# ECU_Revisi.net
KiCad netlist of a schematic drawn in EasyEDA Pro
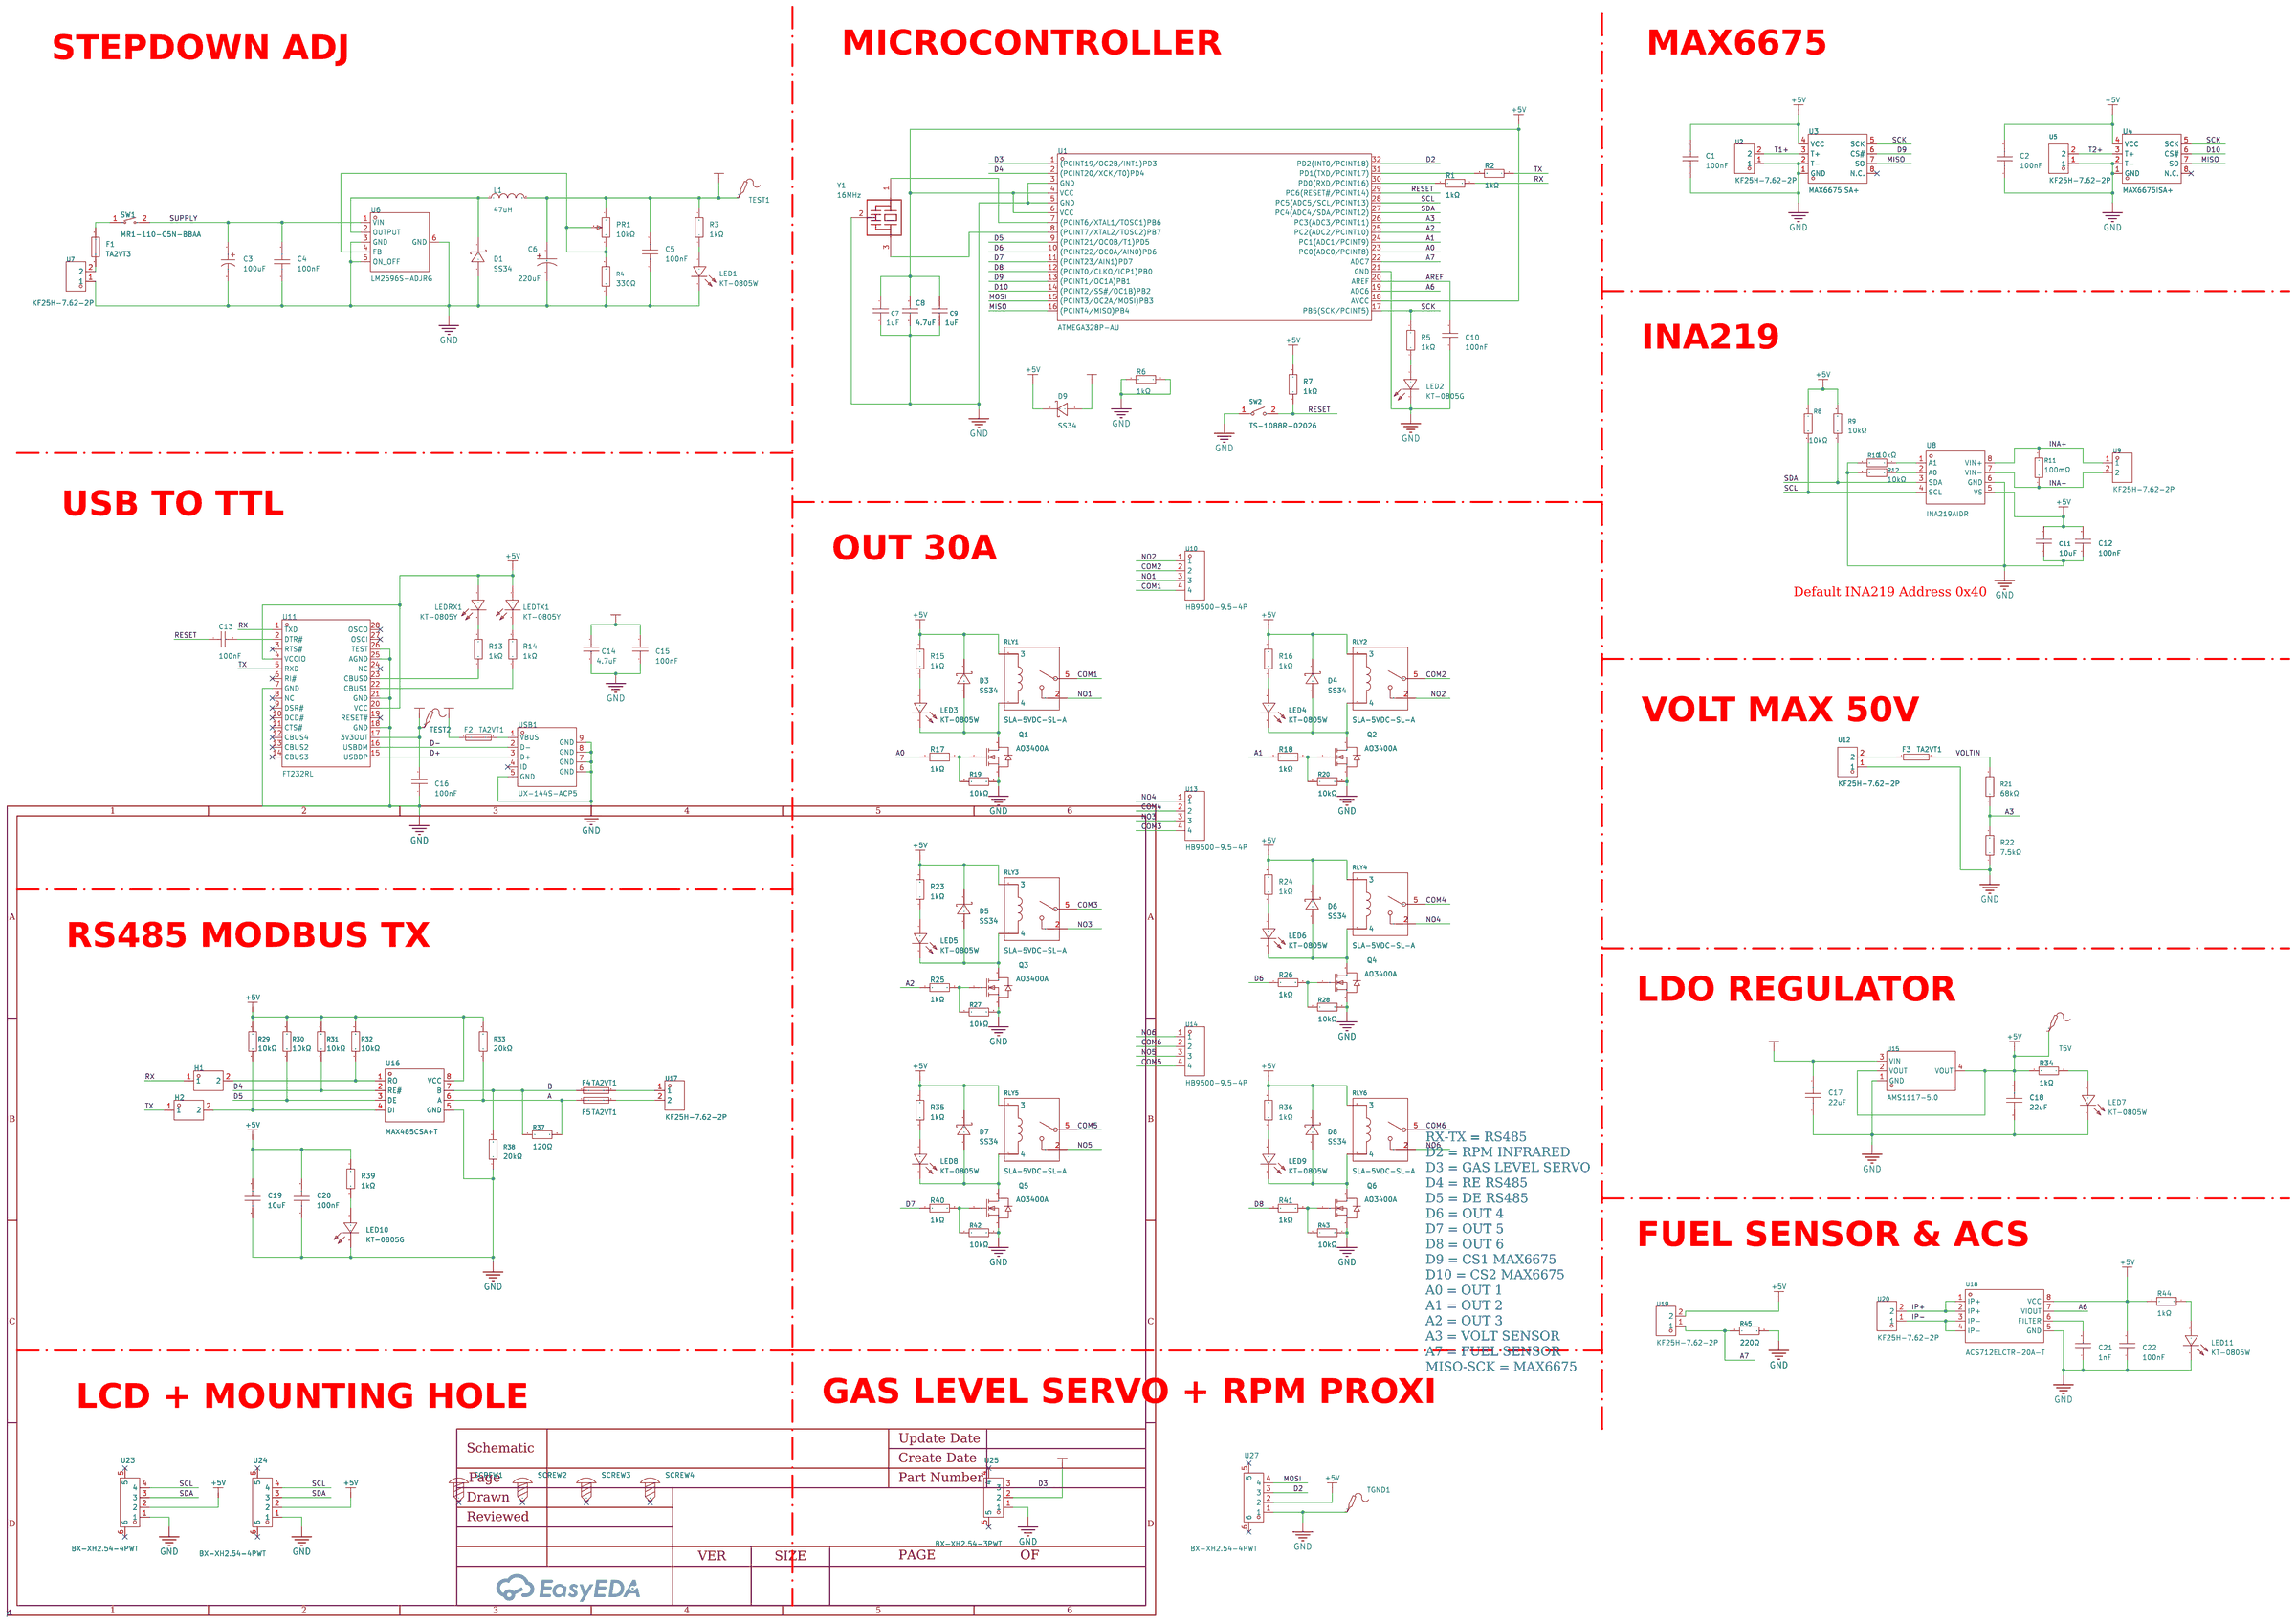
[diagram p0: schematic sheet]

(export (version "E")
  (design (tool "Eeschema 10.0.6"))
  (components
    (comp (ref "C1")
      (value "100nF")
      (footprint "easyedapro:C0805")
      (fields
        (field (name "Manufacturer Part") "CC0805KRX7R9BB104")
        (field (name "Manufacturer") "YAGEO(国巨)")
      )
      (libsource (lib "easyedapro") (part "CC0805KRX7R9BB104"))
    )
    (comp (ref "C2")
      (value "100nF")
      (footprint "easyedapro:C0805")
      (fields
        (field (name "Manufacturer Part") "CC0805KRX7R9BB104")
        (field (name "Manufacturer") "YAGEO(国巨)")
      )
      (libsource (lib "easyedapro") (part "CC0805KRX7R9BB104"))
    )
    (comp (ref "C3")
      (value "100uF")
      (footprint "easyedapro:CAP-SMD_BD8.0-L8.3-W8.3-LS10.0-FD")
      (fields
        (field (name "Manufacturer Part") "VT107M050FA5RR0NB1VP0")
        (field (name "Manufacturer") "CX(承兴)")
      )
      (libsource (lib "easyedapro") (part "VT107M050FA5RR0NB1VP0"))
    )
    (comp (ref "C4")
      (value "100nF")
      (footprint "easyedapro:C0805")
      (fields
        (field (name "Manufacturer Part") "C0805X104K5RAC7210")
        (field (name "Manufacturer") "KEMET(基美)")
      )
      (libsource (lib "easyedapro") (part "C0805X104K5RAC7210"))
    )
    (comp (ref "C5")
      (value "100nF")
      (footprint "easyedapro:C0805")
      (fields
        (field (name "Manufacturer Part") "C0805X104K5RAC7210")
        (field (name "Manufacturer") "KEMET(基美)")
      )
      (libsource (lib "easyedapro") (part "C0805X104K5RAC7210"))
    )
    (comp (ref "C6")
      (value "220uF")
      (footprint "easyedapro:CAP-SMD_BD8.0-L8.3-W8.3-FD")
      (fields (field (name "Manufacturer Part") "VT1V221M0810") (field (name "Manufacturer") "ROQANG(容强)"))
      (libsource (lib "easyedapro") (part "VT1V221M0810"))
    )
    (comp (ref "C7")
      (value "1uF")
      (footprint "easyedapro:C0805")
      (fields
        (field (name "Manufacturer Part") "CL21B105KBFNNNE")
        (field (name "Manufacturer") "SAMSUNG(三星)")
      )
      (libsource (lib "easyedapro") (part "CL21B105KBFNNNE"))
    )
    (comp (ref "C8")
      (value "4.7uF")
      (footprint "easyedapro:C0805")
      (fields
        (field (name "Manufacturer Part") "CL21B475KOFNNNE")
        (field (name "Manufacturer") "SAMSUNG(三星)")
      )
      (libsource (lib "easyedapro") (part "CL21B475KOFNNNE"))
    )
    (comp (ref "C9")
      (value "1uF")
      (footprint "easyedapro:C0805")
      (fields
        (field (name "Manufacturer Part") "CL21B105KBFNNNE")
        (field (name "Manufacturer") "SAMSUNG(三星)")
      )
      (libsource (lib "easyedapro") (part "CL21B105KBFNNNE"))
    )
    (comp (ref "C10")
      (value "100nF")
      (footprint "easyedapro:C0805")
      (fields
        (field (name "Manufacturer Part") "CL21B104KCFNNNE")
        (field (name "Manufacturer") "SAMSUNG(三星)")
      )
      (libsource (lib "easyedapro") (part "CL21B104KCFNNNE"))
    )
    (comp (ref "C11")
      (value "10uF")
      (footprint "easyedapro:C0805")
      (fields
        (field (name "Manufacturer Part") "CL21A106KPFNNNE")
        (field (name "Manufacturer") "SAMSUNG(三星)")
      )
      (libsource (lib "easyedapro") (part "CL21A106KPFNNNE"))
    )
    (comp (ref "C12")
      (value "100nF")
      (footprint "easyedapro:C0805")
      (fields
        (field (name "Manufacturer Part") "CL21B104KCFNNNE")
        (field (name "Manufacturer") "SAMSUNG(三星)")
      )
      (libsource (lib "easyedapro") (part "CL21B104KCFNNNE"))
    )
    (comp (ref "C13")
      (value "100nF")
      (footprint "easyedapro:C0805")
      (fields
        (field (name "Manufacturer Part") "CL21B104KCFNNNE")
        (field (name "Manufacturer") "SAMSUNG(三星)")
      )
      (libsource (lib "easyedapro") (part "CL21B104KCFNNNE"))
    )
    (comp (ref "C14")
      (value "4.7uF")
      (footprint "easyedapro:C0805")
      (fields
        (field (name "Manufacturer Part") "CL21B475KOFNNNE")
        (field (name "Manufacturer") "SAMSUNG(三星)")
      )
      (libsource (lib "easyedapro") (part "CL21B475KOFNNNE"))
    )
    (comp (ref "C15")
      (value "100nF")
      (footprint "easyedapro:C0805")
      (fields
        (field (name "Manufacturer Part") "CL21B104KCFNNNE")
        (field (name "Manufacturer") "SAMSUNG(三星)")
      )
      (libsource (lib "easyedapro") (part "CL21B104KCFNNNE"))
    )
    (comp (ref "C16")
      (value "100nF")
      (footprint "easyedapro:C0805")
      (fields
        (field (name "Manufacturer Part") "CL21B104KCFNNNE")
        (field (name "Manufacturer") "SAMSUNG(三星)")
      )
      (libsource (lib "easyedapro") (part "CL21B104KCFNNNE"))
    )
    (comp (ref "C17")
      (value "22uF")
      (footprint "easyedapro:C0805")
      (fields
        (field (name "Manufacturer Part") "CL21A226MAQNNNE")
        (field (name "Manufacturer") "SAMSUNG(三星)")
      )
      (libsource (lib "easyedapro") (part "CL21A226MAQNNNE"))
    )
    (comp (ref "C18")
      (value "22uF")
      (footprint "easyedapro:C0805")
      (fields
        (field (name "Manufacturer Part") "CL21A226MAQNNNE")
        (field (name "Manufacturer") "SAMSUNG(三星)")
      )
      (libsource (lib "easyedapro") (part "CL21A226MAQNNNE"))
    )
    (comp (ref "C19")
      (value "10uF")
      (footprint "easyedapro:C0805")
      (fields
        (field (name "Manufacturer Part") "CL21A106KAYNNNE")
        (field (name "Manufacturer") "SAMSUNG(三星)")
      )
      (libsource (lib "easyedapro") (part "CL21A106KAYNNNE"))
    )
    (comp (ref "C20")
      (value "100nF")
      (footprint "easyedapro:C0805")
      (fields
        (field (name "Manufacturer Part") "CC0805KRX7R9BB104")
        (field (name "Manufacturer") "YAGEO(国巨)")
      )
      (libsource (lib "easyedapro") (part "CC0805KRX7R9BB104"))
    )
    (comp (ref "C21")
      (value "1nF")
      (footprint "easyedapro:C0805")
      (fields
        (field (name "Manufacturer Part") "CL21B102KBCNNNC")
        (field (name "Manufacturer") "SAMSUNG(三星)")
      )
      (libsource (lib "easyedapro") (part "CL21B102KBCNNNC"))
    )
    (comp (ref "C22")
      (value "100nF")
      (footprint "easyedapro:C0805")
      (fields
        (field (name "Manufacturer Part") "CL21B104KCFNNNE")
        (field (name "Manufacturer") "SAMSUNG(三星)")
      )
      (libsource (lib "easyedapro") (part "CL21B104KCFNNNE"))
    )
    (comp (ref "D1")
      (value "SS34")
      (footprint "easyedapro:SMA_L4.3-W2.6-LS5.2-RD")
      (fields (field (name "Manufacturer") "MDD(辰达半导体)"))
      (libsource (lib "easyedapro") (part "SS34_C8678"))
    )
    (comp (ref "D3")
      (value "SS34")
      (footprint "easyedapro:SMA_L4.3-W2.6-LS5.2-RD")
      (fields (field (name "Manufacturer") "MDD(辰达半导体)"))
      (libsource (lib "easyedapro") (part "SS34_C8678"))
    )
    (comp (ref "D4")
      (value "SS34")
      (footprint "easyedapro:SMA_L4.3-W2.6-LS5.2-RD")
      (fields (field (name "Manufacturer") "MDD(辰达半导体)"))
      (libsource (lib "easyedapro") (part "SS34_C8678"))
    )
    (comp (ref "D5")
      (value "SS34")
      (footprint "easyedapro:SMA_L4.3-W2.6-LS5.2-RD")
      (fields (field (name "Manufacturer") "MDD(辰达半导体)"))
      (libsource (lib "easyedapro") (part "SS34_C8678"))
    )
    (comp (ref "D6")
      (value "SS34")
      (footprint "easyedapro:SMA_L4.3-W2.6-LS5.2-RD")
      (fields (field (name "Manufacturer") "MDD(辰达半导体)"))
      (libsource (lib "easyedapro") (part "SS34_C8678"))
    )
    (comp (ref "D7")
      (value "SS34")
      (footprint "easyedapro:SMA_L4.3-W2.6-LS5.2-RD")
      (fields (field (name "Manufacturer") "MDD(辰达半导体)"))
      (libsource (lib "easyedapro") (part "SS34_C8678"))
    )
    (comp (ref "D8")
      (value "SS34")
      (footprint "easyedapro:SMA_L4.3-W2.6-LS5.2-RD")
      (fields (field (name "Manufacturer") "MDD(辰达半导体)"))
      (libsource (lib "easyedapro") (part "SS34_C8678"))
    )
    (comp (ref "D9")
      (value "SS34")
      (footprint "easyedapro:SMA_L4.3-W2.6-LS5.2-RD")
      (fields (field (name "Manufacturer") "MDD(辰达半导体)"))
      (libsource (lib "easyedapro") (part "SS34_C8678"))
    )
    (comp (ref "F1")
      (value "TA2VT3")
      (footprint "easyedapro:FUSE-SMD_L6.1-W2.5")
      (description "Type:SMD Fuse Current Rating:3A Voltage Rating  (AC):250V")
      (fields (field (name "Manufacturer") "TLC(竞沃)"))
      (libsource (lib "easyedapro") (part "TA2VT3"))
    )
    (comp (ref "F2")
      (value "TA2VT1")
      (footprint "easyedapro:F2410")
      (fields (field (name "Manufacturer") "TLC(竞沃)"))
      (libsource (lib "easyedapro") (part "TA2VT1"))
    )
    (comp (ref "F3")
      (value "TA2VT1")
      (footprint "easyedapro:F2410")
      (fields (field (name "Manufacturer") "TLC(竞沃)"))
      (libsource (lib "easyedapro") (part "TA2VT1"))
    )
    (comp (ref "F4")
      (value "TA2VT1")
      (footprint "easyedapro:F2410")
      (fields (field (name "Manufacturer") "TLC(竞沃)"))
      (libsource (lib "easyedapro") (part "TA2VT1"))
    )
    (comp (ref "F5")
      (value "TA2VT1")
      (footprint "easyedapro:F2410")
      (fields (field (name "Manufacturer") "TLC(竞沃)"))
      (libsource (lib "easyedapro") (part "TA2VT1"))
    )
    (comp (ref "H1")
      (value "~")
      (footprint "easyedapro:HDR-TH_2P-P2.54-V-M-2")
      (libsource (lib "easyedapro") (part "HDR-M-2.54_2x1"))
    )
    (comp (ref "H2")
      (value "~")
      (footprint "easyedapro:HDR-TH_2P-P2.54-V-M-2")
      (libsource (lib "easyedapro") (part "HDR-M-2.54_2x1"))
    )
    (comp (ref "L1")
      (value "47uH")
      (footprint "easyedapro:IND-SMD_L12.0-W12.0_CDRH127NP")
      (fields
        (field (name "Manufacturer Part") "CDRH127NP-470MC")
        (field (name "Manufacturer") "Sumida(胜美达)")
      )
      (libsource (lib "easyedapro") (part "CDRH127NP-470MC"))
    )
    (comp (ref "LED1")
      (value "KT-0805W")
      (footprint "easyedapro:LED0805-R-RD")
      (fields (field (name "Manufacturer") "KENTO"))
      (libsource (lib "easyedapro") (part "whiteLEDSMD"))
    )
    (comp (ref "LED2")
      (value "KT-0805G")
      (footprint "easyedapro:LED0805-R-RD")
      (fields (field (name "Manufacturer") "KENTO"))
      (libsource (lib "easyedapro") (part "0805G (Green)"))
    )
    (comp (ref "LED3")
      (value "KT-0805W")
      (footprint "easyedapro:LED0805-R-RD")
      (fields (field (name "Manufacturer") "KENTO"))
      (libsource (lib "easyedapro") (part "whiteLEDSMD"))
    )
    (comp (ref "LED4")
      (value "KT-0805W")
      (footprint "easyedapro:LED0805-R-RD")
      (fields (field (name "Manufacturer") "KENTO"))
      (libsource (lib "easyedapro") (part "whiteLEDSMD"))
    )
    (comp (ref "LED5")
      (value "KT-0805W")
      (footprint "easyedapro:LED0805-R-RD")
      (fields (field (name "Manufacturer") "KENTO"))
      (libsource (lib "easyedapro") (part "whiteLEDSMD"))
    )
    (comp (ref "LED6")
      (value "KT-0805W")
      (footprint "easyedapro:LED0805-R-RD")
      (fields (field (name "Manufacturer") "KENTO"))
      (libsource (lib "easyedapro") (part "whiteLEDSMD"))
    )
    (comp (ref "LED7")
      (value "KT-0805W")
      (footprint "easyedapro:LED0805-R-RD")
      (fields (field (name "Manufacturer") "KENTO"))
      (libsource (lib "easyedapro") (part "whiteLEDSMD"))
    )
    (comp (ref "LED8")
      (value "KT-0805W")
      (footprint "easyedapro:LED0805-R-RD")
      (fields (field (name "Manufacturer") "KENTO"))
      (libsource (lib "easyedapro") (part "whiteLEDSMD"))
    )
    (comp (ref "LED9")
      (value "KT-0805W")
      (footprint "easyedapro:LED0805-R-RD")
      (fields (field (name "Manufacturer") "KENTO"))
      (libsource (lib "easyedapro") (part "whiteLEDSMD"))
    )
    (comp (ref "LED10")
      (value "KT-0805G")
      (footprint "easyedapro:LED0805-R-RD")
      (fields (field (name "Manufacturer") "KENTO"))
      (libsource (lib "easyedapro") (part "0805G (Green)"))
    )
    (comp (ref "LED11")
      (value "KT-0805W")
      (footprint "easyedapro:LED0805-R-RD")
      (fields (field (name "Manufacturer") "KENTO"))
      (libsource (lib "easyedapro") (part "whiteLEDSMD"))
    )
    (comp (ref "LEDRX1")
      (value "KT-0805Y")
      (footprint "easyedapro:LED0805-R-RD")
      (fields (field (name "Manufacturer") "KENTO"))
      (libsource (lib "easyedapro") (part "17-21SUYC/TR8"))
    )
    (comp (ref "LEDTX1")
      (value "KT-0805Y")
      (footprint "easyedapro:LED0805-R-RD")
      (fields (field (name "Manufacturer") "KENTO"))
      (libsource (lib "easyedapro") (part "17-21SUYC/TR8"))
    )
    (comp (ref "PR1")
      (value "10kΩ")
      (footprint "easyedapro:RES-ADJ-TH_3P-L10.0-W10.0-P2.50-L")
      (libsource (lib "easyedapro") (part "3386P-1-103LF"))
    )
    (comp (ref "Q1")
      (value "AO3400A")
      (footprint "easyedapro:SOT-23-3_L2.9-W1.3-P1.90-LS2.4-BR")
      (fields (field (name "Manufacturer") "AOS"))
      (libsource (lib "easyedapro") (part "AO3400A"))
    )
    (comp (ref "Q2")
      (value "AO3400A")
      (footprint "easyedapro:SOT-23-3_L2.9-W1.3-P1.90-LS2.4-BR")
      (fields (field (name "Manufacturer") "AOS"))
      (libsource (lib "easyedapro") (part "AO3400A"))
    )
    (comp (ref "Q3")
      (value "AO3400A")
      (footprint "easyedapro:SOT-23-3_L2.9-W1.3-P1.90-LS2.4-BR")
      (fields (field (name "Manufacturer") "AOS"))
      (libsource (lib "easyedapro") (part "AO3400A"))
    )
    (comp (ref "Q4")
      (value "AO3400A")
      (footprint "easyedapro:SOT-23-3_L2.9-W1.3-P1.90-LS2.4-BR")
      (fields (field (name "Manufacturer") "AOS"))
      (libsource (lib "easyedapro") (part "AO3400A"))
    )
    (comp (ref "Q5")
      (value "AO3400A")
      (footprint "easyedapro:SOT-23-3_L2.9-W1.3-P1.90-LS2.4-BR")
      (fields (field (name "Manufacturer") "AOS"))
      (libsource (lib "easyedapro") (part "AO3400A"))
    )
    (comp (ref "Q6")
      (value "AO3400A")
      (footprint "easyedapro:SOT-23-3_L2.9-W1.3-P1.90-LS2.4-BR")
      (fields (field (name "Manufacturer") "AOS"))
      (libsource (lib "easyedapro") (part "AO3400A"))
    )
    (comp (ref "R1")
      (value "1kΩ")
      (footprint "easyedapro:R0805")
      (fields
        (field (name "Manufacturer Part") "0805W8F1001T5E")
        (field (name "Manufacturer") "UNI-ROYAL(厚声)")
      )
      (libsource (lib "easyedapro") (part "0805W8F1001T5E"))
    )
    (comp (ref "R2")
      (value "1kΩ")
      (footprint "easyedapro:R0805")
      (fields
        (field (name "Manufacturer Part") "0805W8F1001T5E")
        (field (name "Manufacturer") "UNI-ROYAL(厚声)")
      )
      (libsource (lib "easyedapro") (part "0805W8F1001T5E"))
    )
    (comp (ref "R3")
      (value "1kΩ")
      (footprint "easyedapro:R0805")
      (fields
        (field (name "Manufacturer Part") "0805W8F1001T5E")
        (field (name "Manufacturer") "UNI-ROYAL(厚声)")
      )
      (libsource (lib "easyedapro") (part "0805W8F1001T5E"))
    )
    (comp (ref "R4")
      (value "330Ω")
      (footprint "easyedapro:R0805")
      (fields
        (field (name "Manufacturer Part") "0805W8F3300T5E")
        (field (name "Manufacturer") "UNI-ROYAL(厚声)")
      )
      (libsource (lib "easyedapro") (part "0805W8F3300T5E"))
    )
    (comp (ref "R5")
      (value "1kΩ")
      (footprint "easyedapro:R0805")
      (fields
        (field (name "Manufacturer Part") "0805W8F1001T5E")
        (field (name "Manufacturer") "UNI-ROYAL(厚声)")
      )
      (libsource (lib "easyedapro") (part "0805W8F1001T5E"))
    )
    (comp (ref "R6")
      (value "1kΩ")
      (footprint "easyedapro:R0805")
      (fields
        (field (name "Manufacturer Part") "0805W8F1001T5E")
        (field (name "Manufacturer") "UNI-ROYAL(厚声)")
      )
      (libsource (lib "easyedapro") (part "0805W8F1001T5E"))
    )
    (comp (ref "R7")
      (value "1kΩ")
      (footprint "easyedapro:R0805")
      (fields
        (field (name "Manufacturer Part") "0805W8F1001T5E")
        (field (name "Manufacturer") "UNI-ROYAL(厚声)")
      )
      (libsource (lib "easyedapro") (part "0805W8F1001T5E"))
    )
    (comp (ref "R8")
      (value "10kΩ")
      (footprint "easyedapro:R0805")
      (fields
        (field (name "Manufacturer Part") "0805W8F1002T5E")
        (field (name "Manufacturer") "UNI-ROYAL(厚声)")
      )
      (libsource (lib "easyedapro") (part "0805W8F1002T5E"))
    )
    (comp (ref "R9")
      (value "10kΩ")
      (footprint "easyedapro:R0805")
      (fields
        (field (name "Manufacturer Part") "0805W8F1002T5E")
        (field (name "Manufacturer") "UNI-ROYAL(厚声)")
      )
      (libsource (lib "easyedapro") (part "0805W8F1002T5E"))
    )
    (comp (ref "R10")
      (value "10kΩ")
      (footprint "easyedapro:R0805")
      (fields
        (field (name "Manufacturer Part") "0805W8F1002T5E")
        (field (name "Manufacturer") "UNI-ROYAL(厚声)")
      )
      (libsource (lib "easyedapro") (part "0805W8F1002T5E"))
    )
    (comp (ref "R11")
      (value "100mΩ")
      (footprint "easyedapro:R1206")
      (fields
        (field (name "Manufacturer Part") "1206W4F100LT5E")
        (field (name "Manufacturer") "UNI-ROYAL(厚声)")
      )
      (libsource (lib "easyedapro") (part "1206W4F100LT5E"))
    )
    (comp (ref "R12")
      (value "10kΩ")
      (footprint "easyedapro:R0805")
      (fields
        (field (name "Manufacturer Part") "0805W8F1002T5E")
        (field (name "Manufacturer") "UNI-ROYAL(厚声)")
      )
      (libsource (lib "easyedapro") (part "0805W8F1002T5E"))
    )
    (comp (ref "R13")
      (value "1kΩ")
      (footprint "easyedapro:R0805")
      (fields
        (field (name "Manufacturer Part") "0805W8F1001T5E")
        (field (name "Manufacturer") "UNI-ROYAL(厚声)")
      )
      (libsource (lib "easyedapro") (part "0805W8F1001T5E"))
    )
    (comp (ref "R14")
      (value "1kΩ")
      (footprint "easyedapro:R0805")
      (fields
        (field (name "Manufacturer Part") "0805W8F1001T5E")
        (field (name "Manufacturer") "UNI-ROYAL(厚声)")
      )
      (libsource (lib "easyedapro") (part "0805W8F1001T5E"))
    )
    (comp (ref "R15")
      (value "1kΩ")
      (footprint "easyedapro:R0805")
      (fields
        (field (name "Manufacturer Part") "0805W8F1001T5E")
        (field (name "Manufacturer") "UNI-ROYAL(厚声)")
      )
      (libsource (lib "easyedapro") (part "0805W8F1001T5E"))
    )
    (comp (ref "R16")
      (value "1kΩ")
      (footprint "easyedapro:R0805")
      (fields
        (field (name "Manufacturer Part") "0805W8F1001T5E")
        (field (name "Manufacturer") "UNI-ROYAL(厚声)")
      )
      (libsource (lib "easyedapro") (part "0805W8F1001T5E"))
    )
    (comp (ref "R17")
      (value "1kΩ")
      (footprint "easyedapro:R0805")
      (fields
        (field (name "Manufacturer Part") "0805W8F1001T5E")
        (field (name "Manufacturer") "UNI-ROYAL(厚声)")
      )
      (libsource (lib "easyedapro") (part "0805W8F1001T5E"))
    )
    (comp (ref "R18")
      (value "1kΩ")
      (footprint "easyedapro:R0805")
      (fields
        (field (name "Manufacturer Part") "0805W8F1001T5E")
        (field (name "Manufacturer") "UNI-ROYAL(厚声)")
      )
      (libsource (lib "easyedapro") (part "0805W8F1001T5E"))
    )
    (comp (ref "R19")
      (value "10kΩ")
      (footprint "easyedapro:R0805")
      (fields
        (field (name "Manufacturer Part") "0805W8F1002T5E")
        (field (name "Manufacturer") "UNI-ROYAL(厚声)")
      )
      (libsource (lib "easyedapro") (part "0805W8F1002T5E"))
    )
    (comp (ref "R20")
      (value "10kΩ")
      (footprint "easyedapro:R0805")
      (fields
        (field (name "Manufacturer Part") "0805W8F1002T5E")
        (field (name "Manufacturer") "UNI-ROYAL(厚声)")
      )
      (libsource (lib "easyedapro") (part "0805W8F1002T5E"))
    )
    (comp (ref "R21")
      (value "68kΩ")
      (footprint "easyedapro:R0805")
      (fields
        (field (name "Manufacturer Part") "0805W8F6802T5E")
        (field (name "Manufacturer") "UNI-ROYAL(厚声)")
      )
      (libsource (lib "easyedapro") (part "0805W8F6802T5E"))
    )
    (comp (ref "R22")
      (value "7.5kΩ")
      (footprint "easyedapro:R0805")
      (fields
        (field (name "Manufacturer Part") "0805W8F7501T5E")
        (field (name "Manufacturer") "UNI-ROYAL(厚声)")
      )
      (libsource (lib "easyedapro") (part "0805W8F7501T5E"))
    )
    (comp (ref "R23")
      (value "1kΩ")
      (footprint "easyedapro:R0805")
      (fields
        (field (name "Manufacturer Part") "0805W8F1001T5E")
        (field (name "Manufacturer") "UNI-ROYAL(厚声)")
      )
      (libsource (lib "easyedapro") (part "0805W8F1001T5E"))
    )
    (comp (ref "R24")
      (value "1kΩ")
      (footprint "easyedapro:R0805")
      (fields
        (field (name "Manufacturer Part") "0805W8F1001T5E")
        (field (name "Manufacturer") "UNI-ROYAL(厚声)")
      )
      (libsource (lib "easyedapro") (part "0805W8F1001T5E"))
    )
    (comp (ref "R25")
      (value "1kΩ")
      (footprint "easyedapro:R0805")
      (fields
        (field (name "Manufacturer Part") "0805W8F1001T5E")
        (field (name "Manufacturer") "UNI-ROYAL(厚声)")
      )
      (libsource (lib "easyedapro") (part "0805W8F1001T5E"))
    )
    (comp (ref "R26")
      (value "1kΩ")
      (footprint "easyedapro:R0805")
      (fields
        (field (name "Manufacturer Part") "0805W8F1001T5E")
        (field (name "Manufacturer") "UNI-ROYAL(厚声)")
      )
      (libsource (lib "easyedapro") (part "0805W8F1001T5E"))
    )
    (comp (ref "R27")
      (value "10kΩ")
      (footprint "easyedapro:R0805")
      (fields
        (field (name "Manufacturer Part") "0805W8F1002T5E")
        (field (name "Manufacturer") "UNI-ROYAL(厚声)")
      )
      (libsource (lib "easyedapro") (part "0805W8F1002T5E"))
    )
    (comp (ref "R28")
      (value "10kΩ")
      (footprint "easyedapro:R0805")
      (fields
        (field (name "Manufacturer Part") "0805W8F1002T5E")
        (field (name "Manufacturer") "UNI-ROYAL(厚声)")
      )
      (libsource (lib "easyedapro") (part "0805W8F1002T5E"))
    )
    (comp (ref "R29")
      (value "10kΩ")
      (footprint "easyedapro:R0805")
      (fields
        (field (name "Manufacturer Part") "0805W8F1002T5E")
        (field (name "Manufacturer") "UNI-ROYAL(厚声)")
      )
      (libsource (lib "easyedapro") (part "0805W8F1002T5E"))
    )
    (comp (ref "R30")
      (value "10kΩ")
      (footprint "easyedapro:R0805")
      (fields
        (field (name "Manufacturer Part") "0805W8F1002T5E")
        (field (name "Manufacturer") "UNI-ROYAL(厚声)")
      )
      (libsource (lib "easyedapro") (part "0805W8F1002T5E"))
    )
    (comp (ref "R31")
      (value "10kΩ")
      (footprint "easyedapro:R0805")
      (fields
        (field (name "Manufacturer Part") "0805W8F1002T5E")
        (field (name "Manufacturer") "UNI-ROYAL(厚声)")
      )
      (libsource (lib "easyedapro") (part "0805W8F1002T5E"))
    )
    (comp (ref "R32")
      (value "10kΩ")
      (footprint "easyedapro:R0805")
      (fields
        (field (name "Manufacturer Part") "0805W8F1002T5E")
        (field (name "Manufacturer") "UNI-ROYAL(厚声)")
      )
      (libsource (lib "easyedapro") (part "0805W8F1002T5E"))
    )
    (comp (ref "R33")
      (value "20kΩ")
      (footprint "easyedapro:R0805")
      (fields
        (field (name "Manufacturer Part") "0805W8F2002T5E")
        (field (name "Manufacturer") "UNI-ROYAL(厚声)")
      )
      (libsource (lib "easyedapro") (part "0805W8F2002T5E"))
    )
    (comp (ref "R34")
      (value "1kΩ")
      (footprint "easyedapro:R0805")
      (fields
        (field (name "Manufacturer Part") "0805W8F1001T5E")
        (field (name "Manufacturer") "UNI-ROYAL(厚声)")
      )
      (libsource (lib "easyedapro") (part "0805W8F1001T5E"))
    )
    (comp (ref "R35")
      (value "1kΩ")
      (footprint "easyedapro:R0805")
      (fields
        (field (name "Manufacturer Part") "0805W8F1001T5E")
        (field (name "Manufacturer") "UNI-ROYAL(厚声)")
      )
      (libsource (lib "easyedapro") (part "0805W8F1001T5E"))
    )
    (comp (ref "R36")
      (value "1kΩ")
      (footprint "easyedapro:R0805")
      (fields
        (field (name "Manufacturer Part") "0805W8F1001T5E")
        (field (name "Manufacturer") "UNI-ROYAL(厚声)")
      )
      (libsource (lib "easyedapro") (part "0805W8F1001T5E"))
    )
    (comp (ref "R37")
      (value "120Ω")
      (footprint "easyedapro:R0805")
      (fields
        (field (name "Manufacturer Part") "0805W8F1200T5E")
        (field (name "Manufacturer") "UNI-ROYAL(厚声)")
      )
      (libsource (lib "easyedapro") (part "0805W8F1200T5E"))
    )
    (comp (ref "R38")
      (value "20kΩ")
      (footprint "easyedapro:R0805")
      (fields
        (field (name "Manufacturer Part") "0805W8F2002T5E")
        (field (name "Manufacturer") "UNI-ROYAL(厚声)")
      )
      (libsource (lib "easyedapro") (part "0805W8F2002T5E"))
    )
    (comp (ref "R39")
      (value "1kΩ")
      (footprint "easyedapro:R0805")
      (fields
        (field (name "Manufacturer Part") "0805W8F1001T5E")
        (field (name "Manufacturer") "UNI-ROYAL(厚声)")
      )
      (libsource (lib "easyedapro") (part "0805W8F1001T5E"))
    )
    (comp (ref "R40")
      (value "1kΩ")
      (footprint "easyedapro:R0805")
      (fields
        (field (name "Manufacturer Part") "0805W8F1001T5E")
        (field (name "Manufacturer") "UNI-ROYAL(厚声)")
      )
      (libsource (lib "easyedapro") (part "0805W8F1001T5E"))
    )
    (comp (ref "R41")
      (value "1kΩ")
      (footprint "easyedapro:R0805")
      (fields
        (field (name "Manufacturer Part") "0805W8F1001T5E")
        (field (name "Manufacturer") "UNI-ROYAL(厚声)")
      )
      (libsource (lib "easyedapro") (part "0805W8F1001T5E"))
    )
    (comp (ref "R42")
      (value "10kΩ")
      (footprint "easyedapro:R0805")
      (fields
        (field (name "Manufacturer Part") "0805W8F1002T5E")
        (field (name "Manufacturer") "UNI-ROYAL(厚声)")
      )
      (libsource (lib "easyedapro") (part "0805W8F1002T5E"))
    )
    (comp (ref "R43")
      (value "10kΩ")
      (footprint "easyedapro:R0805")
      (fields
        (field (name "Manufacturer Part") "0805W8F1002T5E")
        (field (name "Manufacturer") "UNI-ROYAL(厚声)")
      )
      (libsource (lib "easyedapro") (part "0805W8F1002T5E"))
    )
    (comp (ref "R44")
      (value "1kΩ")
      (footprint "easyedapro:R0805")
      (fields
        (field (name "Manufacturer Part") "0805W8F1001T5E")
        (field (name "Manufacturer") "UNI-ROYAL(厚声)")
      )
      (libsource (lib "easyedapro") (part "0805W8F1001T5E"))
    )
    (comp (ref "R45")
      (value "220Ω")
      (footprint "easyedapro:R0805")
      (fields
        (field (name "Manufacturer Part") "0805W8F2200T5E")
        (field (name "Manufacturer") "UNI-ROYAL(厚声)")
      )
      (libsource (lib "easyedapro") (part "0805W8F2200T5E"))
    )
    (comp (ref "RLY1")
      (value "SLA-5VDC-SL-A")
      (footprint "easyedapro:RELAY-TH_SLA-XXVDC-SL-A")
      (fields (field (name "Manufacturer") "松乐"))
      (libsource (lib "easyedapro") (part "SLA-5VDC-SL-A"))
    )
    (comp (ref "RLY2")
      (value "SLA-5VDC-SL-A")
      (footprint "easyedapro:RELAY-TH_SLA-XXVDC-SL-A")
      (fields (field (name "Manufacturer") "松乐"))
      (libsource (lib "easyedapro") (part "SLA-5VDC-SL-A"))
    )
    (comp (ref "RLY3")
      (value "SLA-5VDC-SL-A")
      (footprint "easyedapro:RELAY-TH_SLA-XXVDC-SL-A")
      (fields (field (name "Manufacturer") "松乐"))
      (libsource (lib "easyedapro") (part "SLA-5VDC-SL-A"))
    )
    (comp (ref "RLY4")
      (value "SLA-5VDC-SL-A")
      (footprint "easyedapro:RELAY-TH_SLA-XXVDC-SL-A")
      (fields (field (name "Manufacturer") "松乐"))
      (libsource (lib "easyedapro") (part "SLA-5VDC-SL-A"))
    )
    (comp (ref "RLY5")
      (value "SLA-5VDC-SL-A")
      (footprint "easyedapro:RELAY-TH_SLA-XXVDC-SL-A")
      (fields (field (name "Manufacturer") "松乐"))
      (libsource (lib "easyedapro") (part "SLA-5VDC-SL-A"))
    )
    (comp (ref "RLY6")
      (value "SLA-5VDC-SL-A")
      (footprint "easyedapro:RELAY-TH_SLA-XXVDC-SL-A")
      (fields (field (name "Manufacturer") "松乐"))
      (libsource (lib "easyedapro") (part "SLA-5VDC-SL-A"))
    )
    (comp (ref "SCREW1")
      (value "~")
      (footprint "easyedapro:Screw-Hole-M4")
      (description "Screw-Hole-M4")
      (libsource (lib "easyedapro") (part "Screw-Hole"))
    )
    (comp (ref "SCREW2")
      (value "~")
      (footprint "easyedapro:Screw-Hole-M4")
      (description "Screw-Hole-M4")
      (libsource (lib "easyedapro") (part "Screw-Hole"))
    )
    (comp (ref "SCREW3")
      (value "~")
      (footprint "easyedapro:Screw-Hole-M4")
      (description "Screw-Hole-M4")
      (libsource (lib "easyedapro") (part "Screw-Hole"))
    )
    (comp (ref "SCREW4")
      (value "~")
      (footprint "easyedapro:Screw-Hole-M4")
      (description "Screw-Hole-M4")
      (libsource (lib "easyedapro") (part "Screw-Hole"))
    )
    (comp (ref "SW1")
      (value "MR1-110-C5N-BBAA")
      (footprint "easyedapro:SW-TH_MR1-110-C5N-BBAA")
      (fields (field (name "Manufacturer") "HONGJU(宏聚)"))
      (libsource (lib "easyedapro") (part "MR1-110-C5N-BBAA"))
    )
    (comp (ref "SW2")
      (value "TS-1088R-02026")
      (footprint "easyedapro:SW-SMD_L3.9-W3.0-P4.45")
      (fields (field (name "Manufacturer") "XUNPU(讯普)"))
      (libsource (lib "easyedapro") (part "TS-1088R-02026"))
    )
    (comp (ref "T5V")
      (value "~")
      (footprint "easyedapro:Test-Point-0.5mm")
      (description "Test Point 测试点")
      (libsource (lib "easyedapro") (part "Test-Point"))
    )
    (comp (ref "TEST1")
      (value "~")
      (footprint "easyedapro:Test-Point-0.5mm")
      (description "Test Point 测试点")
      (libsource (lib "easyedapro") (part "Test-Point"))
    )
    (comp (ref "TEST2")
      (value "~")
      (footprint "easyedapro:Test-Point-0.5mm")
      (description "Test Point 测试点")
      (libsource (lib "easyedapro") (part "Test-Point"))
    )
    (comp (ref "TGND1")
      (value "~")
      (footprint "easyedapro:Test-Point-0.5mm")
      (description "Test Point 测试点")
      (libsource (lib "easyedapro") (part "Test-Point"))
    )
    (comp (ref "U1")
      (value "ATMEGA328P-AU")
      (footprint "easyedapro:TQFP-32_L7.0-W7.0-P0.80-LS9.0-BL")
      (libsource (lib "easyedapro") (part "ATMEGA328P-AU_C2851158"))
    )
    (comp (ref "U2")
      (value "KF25H-7.62-2P")
      (footprint "easyedapro:CONN-TH_KF25H-7.62-2P")
      (fields (field (name "Manufacturer") "KEFA(科发)"))
      (libsource (lib "easyedapro") (part "KF25H-7.62-2P"))
    )
    (comp (ref "U3")
      (value "MAX6675ISA+")
      (footprint "easyedapro:SOIC-8_L5.0-W4.0-P1.27-LS6.0-BL")
      (fields (field (name "Manufacturer") "ADI(亚德诺)/MAXIM(美信)"))
      (libsource (lib "easyedapro") (part "MAX6675ISA+"))
    )
    (comp (ref "U4")
      (value "MAX6675ISA+")
      (footprint "easyedapro:SOIC-8_L5.0-W4.0-P1.27-LS6.0-BL")
      (fields (field (name "Manufacturer") "ADI(亚德诺)/MAXIM(美信)"))
      (libsource (lib "easyedapro") (part "MAX6675ISA+"))
    )
    (comp (ref "U5")
      (value "KF25H-7.62-2P")
      (footprint "easyedapro:CONN-TH_KF25H-7.62-2P")
      (fields (field (name "Manufacturer") "KEFA(科发)"))
      (libsource (lib "easyedapro") (part "KF25H-7.62-2P"))
    )
    (comp (ref "U6")
      (value "LM2596S-ADJRG")
      (footprint "easyedapro:TO-263-5_L10.2-W8.6-P1.70-LS14.4-TL")
      (fields (field (name "Manufacturer") "HGC(深圳汉芯)"))
      (libsource (lib "easyedapro") (part "LM2596S-ADJRG"))
    )
    (comp (ref "U7")
      (value "KF25H-7.62-2P")
      (footprint "easyedapro:CONN-TH_KF25H-7.62-2P")
      (fields (field (name "Manufacturer") "KEFA(科发)"))
      (libsource (lib "easyedapro") (part "KF25H-7.62-2P"))
    )
    (comp (ref "U8")
      (value "INA219AIDR")
      (footprint "easyedapro:SOIC-8_L4.9-W3.9-P1.27-LS6.0-BL")
      (fields (field (name "Manufacturer") "TI(德州仪器)"))
      (libsource (lib "easyedapro") (part "INA219AIDR"))
    )
    (comp (ref "U9")
      (value "KF25H-7.62-2P")
      (footprint "easyedapro:CONN-TH_KF25H-7.62-2P")
      (fields (field (name "Manufacturer") "KEFA(科发)"))
      (libsource (lib "easyedapro") (part "KF25H-7.62-2P"))
    )
    (comp (ref "U10")
      (value "HB9500-9.5-4P")
      (footprint "easyedapro:CONN-TH_HB9500-9.5-4P")
      (fields (field (name "Manufacturer") "KEFA(科发)"))
      (libsource (lib "easyedapro") (part "HB9500-9.5-4P"))
    )
    (comp (ref "U11")
      (value "FT232RL")
      (footprint "easyedapro:SSOP-28_L10.2-W5.3-P0.65-LS7.8-BL")
      (fields (field (name "Manufacturer") "FTDI(飞特帝亚)"))
      (libsource (lib "easyedapro") (part "FT232RL"))
    )
    (comp (ref "U12")
      (value "KF25H-7.62-2P")
      (footprint "easyedapro:CONN-TH_KF25H-7.62-2P")
      (fields (field (name "Manufacturer") "KEFA(科发)"))
      (libsource (lib "easyedapro") (part "KF25H-7.62-2P"))
    )
    (comp (ref "U13")
      (value "HB9500-9.5-4P")
      (footprint "easyedapro:CONN-TH_HB9500-9.5-4P")
      (fields (field (name "Manufacturer") "KEFA(科发)"))
      (libsource (lib "easyedapro") (part "HB9500-9.5-4P"))
    )
    (comp (ref "U14")
      (value "HB9500-9.5-4P")
      (footprint "easyedapro:CONN-TH_HB9500-9.5-4P")
      (fields (field (name "Manufacturer") "KEFA(科发)"))
      (libsource (lib "easyedapro") (part "HB9500-9.5-4P"))
    )
    (comp (ref "U15")
      (value "AMS1117-5.0")
      (footprint "easyedapro:SOT-223_L6.5-W3.5-P2.30-LS7.0-BR")
      (fields (field (name "Manufacturer") "AMS"))
      (libsource (lib "easyedapro") (part "AMS1117-5.0"))
    )
    (comp (ref "U16")
      (value "MAX485CSA+T")
      (footprint "easyedapro:SOIC-8_L4.9-W3.9-P1.27-LS6.0-BL")
      (fields (field (name "Manufacturer") "ADI(亚德诺)/MAXIM(美信)"))
      (libsource (lib "easyedapro") (part "MAX485CSA+T"))
    )
    (comp (ref "U17")
      (value "KF25H-7.62-2P")
      (footprint "easyedapro:CONN-TH_KF25H-7.62-2P")
      (fields (field (name "Manufacturer") "KEFA(科发)"))
      (libsource (lib "easyedapro") (part "KF25H-7.62-2P"))
    )
    (comp (ref "U18")
      (value "ACS712ELCTR-20A-T")
      (footprint "easyedapro:SOIC-8_L4.9-W3.9-P1.27-LS6.0-BL")
      (fields (field (name "Manufacturer") "ALLEGRO(美国埃戈罗)"))
      (libsource (lib "easyedapro") (part "ACS712ELCTR-20A-T"))
    )
    (comp (ref "U19")
      (value "KF25H-7.62-2P")
      (footprint "easyedapro:CONN-TH_KF25H-7.62-2P")
      (fields (field (name "Manufacturer") "KEFA(科发)"))
      (libsource (lib "easyedapro") (part "KF25H-7.62-2P"))
    )
    (comp (ref "U20")
      (value "KF25H-7.62-2P")
      (footprint "easyedapro:CONN-TH_KF25H-7.62-2P")
      (fields (field (name "Manufacturer") "KEFA(科发)"))
      (libsource (lib "easyedapro") (part "KF25H-7.62-2P"))
    )
    (comp (ref "U23")
      (value "BX-XH2.54-4PWT")
      (footprint "easyedapro:CONN-SMD_4P-P2.50_BX-XH2.54-4PWT")
      (fields (field (name "Manufacturer") "Bossie(博锡)"))
      (libsource (lib "easyedapro") (part "BX-XH2.54-4PWT"))
    )
    (comp (ref "U24")
      (value "BX-XH2.54-4PWT")
      (footprint "easyedapro:CONN-SMD_4P-P2.50_BX-XH2.54-4PWT")
      (fields (field (name "Manufacturer") "Bossie(博锡)"))
      (libsource (lib "easyedapro") (part "BX-XH2.54-4PWT"))
    )
    (comp (ref "U25")
      (value "BX-XH2.54-3PWT")
      (footprint "easyedapro:CONN-SMD_3P-P2.50_BX-XH2.54-3PWT")
      (fields (field (name "Manufacturer") "Bossie(博锡)"))
      (libsource (lib "easyedapro") (part "BX-XH2.54-3PWT"))
    )
    (comp (ref "U27")
      (value "BX-XH2.54-4PWT")
      (footprint "easyedapro:CONN-SMD_4P-P2.50_BX-XH2.54-4PWT")
      (fields (field (name "Manufacturer") "Bossie(博锡)"))
      (libsource (lib "easyedapro") (part "BX-XH2.54-4PWT"))
    )
    (comp (ref "USB1")
      (value "UX-144S-ACP5")
      (footprint "easyedapro:MINI-USB-SMD_UX-144S-ACP5")
      (fields (field (name "Manufacturer") "XUNPU(讯普)"))
      (libsource (lib "easyedapro") (part "UX-144S-ACP5"))
    )
    (comp (ref "Y1")
      (value "16MHz")
      (footprint "easyedapro:OSC-SMD_3P-L3.2-W1.3-P1.2-L")
      (fields
        (field (name "Manufacturer Part") "CSTCE16M0V53Z-R0")
        (field (name "Manufacturer") "muRata(村田)")
      )
      (libsource (lib "easyedapro") (part "CSTCE16M0V53Z-R0"))
    )
  )
  (nets
    (net (code "1") (name "+3.3V") (class "Default")
      (node (ref "C16") (pin "2") (pinfunction "2_2") (pintype "input"))
      (node (ref "TEST2") (pin "1") (pinfunction "1_1") (pintype "unspecified"))
      (node (ref "U11") (pin "17") (pinfunction "3V3OUT_17") (pintype "unspecified"))
    )
    (net (code "2") (name "+5V") (class "Default")
      (node (ref "C1") (pin "2") (pinfunction "2_2") (pintype "unspecified"))
      (node (ref "C11") (pin "2") (pinfunction "2_2") (pintype "input"))
      (node (ref "C12") (pin "2") (pinfunction "2_2") (pintype "input"))
      (node (ref "C18") (pin "2") (pinfunction "2_2") (pintype "unspecified"))
      (node (ref "C19") (pin "2") (pinfunction "2_2") (pintype "unspecified"))
      (node (ref "C2") (pin "2") (pinfunction "2_2") (pintype "unspecified"))
      (node (ref "C20") (pin "2") (pinfunction "2_2") (pintype "unspecified"))
      (node (ref "C22") (pin "2") (pinfunction "2_2") (pintype "input"))
      (node (ref "C7") (pin "2") (pinfunction "2_2") (pintype "input"))
      (node (ref "C8") (pin "2") (pinfunction "2_2") (pintype "input"))
      (node (ref "C9") (pin "2") (pinfunction "2_2") (pintype "input"))
      (node (ref "D3") (pin "1") (pinfunction "K_1") (pintype "unspecified"))
      (node (ref "D4") (pin "1") (pinfunction "K_1") (pintype "unspecified"))
      (node (ref "D5") (pin "1") (pinfunction "K_1") (pintype "unspecified"))
      (node (ref "D6") (pin "1") (pinfunction "K_1") (pintype "unspecified"))
      (node (ref "D7") (pin "1") (pinfunction "K_1") (pintype "unspecified"))
      (node (ref "D8") (pin "1") (pinfunction "K_1") (pintype "unspecified"))
      (node (ref "D9") (pin "1") (pinfunction "K_1") (pintype "unspecified"))
      (node (ref "LEDRX1") (pin "1") (pinfunction "+_1") (pintype "unspecified"))
      (node (ref "LEDTX1") (pin "1") (pinfunction "+_1") (pintype "unspecified"))
      (node (ref "R15") (pin "2") (pinfunction "2_2") (pintype "input"))
      (node (ref "R16") (pin "2") (pinfunction "2_2") (pintype "input"))
      (node (ref "R23") (pin "2") (pinfunction "2_2") (pintype "input"))
      (node (ref "R24") (pin "2") (pinfunction "2_2") (pintype "input"))
      (node (ref "R29") (pin "2") (pinfunction "2_2") (pintype "input"))
      (node (ref "R30") (pin "2") (pinfunction "2_2") (pintype "input"))
      (node (ref "R31") (pin "2") (pinfunction "2_2") (pintype "input"))
      (node (ref "R32") (pin "2") (pinfunction "2_2") (pintype "input"))
      (node (ref "R33") (pin "2") (pinfunction "2_2") (pintype "input"))
      (node (ref "R34") (pin "2") (pinfunction "2_2") (pintype "input"))
      (node (ref "R35") (pin "2") (pinfunction "2_2") (pintype "input"))
      (node (ref "R36") (pin "2") (pinfunction "2_2") (pintype "input"))
      (node (ref "R39") (pin "2") (pinfunction "2_2") (pintype "input"))
      (node (ref "R44") (pin "2") (pinfunction "2_2") (pintype "input"))
      (node (ref "R7") (pin "2") (pinfunction "2_2") (pintype "input"))
      (node (ref "R8") (pin "1") (pinfunction "1_1") (pintype "input"))
      (node (ref "R9") (pin "2") (pinfunction "2_2") (pintype "input"))
      (node (ref "RLY1") (pin "3") (pinfunction "3_3") (pintype "input"))
      (node (ref "RLY2") (pin "3") (pinfunction "3_3") (pintype "input"))
      (node (ref "RLY3") (pin "3") (pinfunction "3_3") (pintype "input"))
      (node (ref "RLY4") (pin "3") (pinfunction "3_3") (pintype "input"))
      (node (ref "RLY5") (pin "3") (pinfunction "3_3") (pintype "input"))
      (node (ref "RLY6") (pin "3") (pinfunction "3_3") (pintype "input"))
      (node (ref "T5V") (pin "1") (pinfunction "1_1") (pintype "unspecified"))
      (node (ref "U1") (pin "18") (pinfunction "AVCC_18") (pintype "unspecified"))
      (node (ref "U1") (pin "4") (pinfunction "VCC_4") (pintype "unspecified"))
      (node (ref "U1") (pin "6") (pinfunction "VCC_6") (pintype "unspecified"))
      (node (ref "U11") (pin "20") (pinfunction "VCC_20") (pintype "unspecified"))
      (node (ref "U11") (pin "4") (pinfunction "VCCIO_4") (pintype "unspecified"))
      (node (ref "U15") (pin "2") (pinfunction "VOUT_2") (pintype "input"))
      (node (ref "U15") (pin "4") (pinfunction "VOUT_4") (pintype "input"))
      (node (ref "U16") (pin "8") (pinfunction "VCC_8") (pintype "unspecified"))
      (node (ref "U18") (pin "8") (pinfunction "VCC_8") (pintype "input"))
      (node (ref "U19") (pin "2") (pinfunction "2_2") (pintype "input"))
      (node (ref "U23") (pin "2") (pinfunction "2_2") (pintype "unspecified"))
      (node (ref "U24") (pin "2") (pinfunction "2_2") (pintype "unspecified"))
      (node (ref "U27") (pin "2") (pinfunction "2_2") (pintype "unspecified"))
      (node (ref "U3") (pin "4") (pinfunction "VCC_4") (pintype "unspecified"))
      (node (ref "U4") (pin "4") (pinfunction "VCC_4") (pintype "unspecified"))
      (node (ref "U8") (pin "5") (pinfunction "VS_5") (pintype "unspecified"))
    )
    (net (code "3") (name "+ADJV") (class "Default")
      (node (ref "C17") (pin "2") (pinfunction "2_2") (pintype "unspecified"))
      (node (ref "C5") (pin "2") (pinfunction "2_2") (pintype "unspecified"))
      (node (ref "C6") (pin "1") (pinfunction "1_1") (pintype "unspecified"))
      (node (ref "L1") (pin "2") (pinfunction "2_2") (pintype "unspecified"))
      (node (ref "PR1") (pin "1") (pinfunction "1_1") (pintype "input"))
      (node (ref "R3") (pin "2") (pinfunction "2_2") (pintype "input"))
      (node (ref "TEST1") (pin "1") (pinfunction "1_1") (pintype "unspecified"))
      (node (ref "U15") (pin "3") (pinfunction "VIN_3") (pintype "input"))
      (node (ref "U25") (pin "2") (pinfunction "2_2") (pintype "unspecified"))
    )
    (net (code "4") (name "/A") (class "Default")
      (node (ref "F5") (pin "1") (pinfunction "1_1") (pintype "unspecified"))
      (node (ref "R33") (pin "1") (pinfunction "1_1") (pintype "input"))
      (node (ref "R37") (pin "2") (pinfunction "2_2") (pintype "input"))
      (node (ref "U16") (pin "6") (pinfunction "A_6") (pintype "unspecified"))
    )
    (net (code "5") (name "/A0") (class "Default")
      (node (ref "R17") (pin "1") (pinfunction "1_1") (pintype "input"))
      (node (ref "U1") (pin "23") (pinfunction "PC0(ADC0/PCINT8)_23") (pintype "unspecified"))
    )
    (net (code "6") (name "/A1") (class "Default")
      (node (ref "R18") (pin "1") (pinfunction "1_1") (pintype "input"))
      (node (ref "U1") (pin "24") (pinfunction "PC1(ADC1/PCINT9)_24") (pintype "unspecified"))
    )
    (net (code "7") (name "/A2") (class "Default")
      (node (ref "R25") (pin "1") (pinfunction "1_1") (pintype "input"))
      (node (ref "U1") (pin "25") (pinfunction "PC2(ADC2/PCINT10)_25") (pintype "unspecified"))
    )
    (net (code "8") (name "/A3") (class "Default")
      (node (ref "R21") (pin "1") (pinfunction "1_1") (pintype "input"))
      (node (ref "R22") (pin "2") (pinfunction "2_2") (pintype "input"))
      (node (ref "U1") (pin "26") (pinfunction "PC3(ADC3/PCINT11)_26") (pintype "unspecified"))
    )
    (net (code "9") (name "/A6") (class "Default")
      (node (ref "U1") (pin "19") (pinfunction "ADC6_19") (pintype "unspecified"))
      (node (ref "U18") (pin "7") (pinfunction "VIOUT_7") (pintype "input"))
    )
    (net (code "10") (name "/A7") (class "Default")
      (node (ref "R45") (pin "1") (pinfunction "1_1") (pintype "input"))
      (node (ref "U1") (pin "22") (pinfunction "ADC7_22") (pintype "unspecified"))
      (node (ref "U19") (pin "1") (pinfunction "1_1") (pintype "input"))
    )
    (net (code "11") (name "/AREF") (class "Default")
      (node (ref "C10") (pin "2") (pinfunction "2_2") (pintype "input"))
      (node (ref "U1") (pin "20") (pinfunction "AREF_20") (pintype "unspecified"))
    )
    (net (code "12") (name "/B") (class "Default")
      (node (ref "F4") (pin "1") (pinfunction "1_1") (pintype "unspecified"))
      (node (ref "R37") (pin "1") (pinfunction "1_1") (pintype "input"))
      (node (ref "R38") (pin "2") (pinfunction "2_2") (pintype "input"))
      (node (ref "U16") (pin "7") (pinfunction "B_7") (pintype "unspecified"))
    )
    (net (code "13") (name "/COM1") (class "Default")
      (node (ref "RLY1") (pin "5") (pinfunction "5_5") (pintype "input"))
      (node (ref "U10") (pin "4") (pinfunction "4_4") (pintype "input"))
    )
    (net (code "14") (name "/COM2") (class "Default")
      (node (ref "RLY2") (pin "5") (pinfunction "5_5") (pintype "input"))
      (node (ref "U10") (pin "2") (pinfunction "2_2") (pintype "input"))
    )
    (net (code "15") (name "/COM3") (class "Default")
      (node (ref "RLY3") (pin "5") (pinfunction "5_5") (pintype "input"))
      (node (ref "U13") (pin "4") (pinfunction "4_4") (pintype "input"))
    )
    (net (code "16") (name "/COM4") (class "Default")
      (node (ref "RLY4") (pin "5") (pinfunction "5_5") (pintype "input"))
      (node (ref "U13") (pin "2") (pinfunction "2_2") (pintype "input"))
    )
    (net (code "17") (name "/COM5") (class "Default")
      (node (ref "RLY5") (pin "5") (pinfunction "5_5") (pintype "input"))
      (node (ref "U14") (pin "4") (pinfunction "4_4") (pintype "input"))
    )
    (net (code "18") (name "/COM6") (class "Default")
      (node (ref "RLY6") (pin "5") (pinfunction "5_5") (pintype "input"))
      (node (ref "U14") (pin "2") (pinfunction "2_2") (pintype "input"))
    )
    (net (code "19") (name "/D+") (class "Default")
      (node (ref "U11") (pin "15") (pinfunction "USBDP_15") (pintype "unspecified"))
      (node (ref "USB1") (pin "3") (pinfunction "D+_3") (pintype "unspecified"))
    )
    (net (code "20") (name "/D-") (class "Default")
      (node (ref "U11") (pin "16") (pinfunction "USBDM_16") (pintype "unspecified"))
      (node (ref "USB1") (pin "2") (pinfunction "D-_2") (pintype "unspecified"))
    )
    (net (code "21") (name "/D2") (class "Default")
      (node (ref "U1") (pin "32") (pinfunction "PD2(INT0/PCINT18)_32") (pintype "unspecified"))
      (node (ref "U27") (pin "3") (pinfunction "3_3") (pintype "unspecified"))
    )
    (net (code "22") (name "/D3") (class "Default")
      (node (ref "U1") (pin "1") (pinfunction "(PCINT19/OC2B/INT1)PD3_1") (pintype "unspecified"))
      (node (ref "U25") (pin "3") (pinfunction "3_3") (pintype "unspecified"))
    )
    (net (code "23") (name "/D4") (class "Default")
      (node (ref "R31") (pin "1") (pinfunction "1_1") (pintype "input"))
      (node (ref "U1") (pin "2") (pinfunction "(PCINT20/XCK/T0)PD4_2") (pintype "unspecified"))
      (node (ref "U16") (pin "2") (pinfunction "RE#_2") (pintype "unspecified"))
    )
    (net (code "24") (name "/D5") (class "Default")
      (node (ref "R30") (pin "1") (pinfunction "1_1") (pintype "input"))
      (node (ref "U1") (pin "9") (pinfunction "(PCINT21/OC0B/T1)PD5_9") (pintype "unspecified"))
      (node (ref "U16") (pin "3") (pinfunction "DE_3") (pintype "unspecified"))
    )
    (net (code "25") (name "/D6") (class "Default")
      (node (ref "R26") (pin "1") (pinfunction "1_1") (pintype "input"))
      (node (ref "U1") (pin "10") (pinfunction "(PCINT22/OC0A/AIN0)PD6_10") (pintype "unspecified"))
    )
    (net (code "26") (name "/D7") (class "Default")
      (node (ref "R40") (pin "1") (pinfunction "1_1") (pintype "input"))
      (node (ref "U1") (pin "11") (pinfunction "(PCINT23/AIN1)PD7_11") (pintype "unspecified"))
    )
    (net (code "27") (name "/D8") (class "Default")
      (node (ref "R41") (pin "1") (pinfunction "1_1") (pintype "input"))
      (node (ref "U1") (pin "12") (pinfunction "(PCINT0/CLKO/ICP1)PB0_12") (pintype "unspecified"))
    )
    (net (code "28") (name "/D9") (class "Default")
      (node (ref "U1") (pin "13") (pinfunction "(PCINT1/OC1A)PB1_13") (pintype "unspecified"))
      (node (ref "U3") (pin "6") (pinfunction "CS#_6") (pintype "unspecified"))
    )
    (net (code "29") (name "/D10") (class "Default")
      (node (ref "U1") (pin "14") (pinfunction "(PCINT2/SS#/OC1B)PB2_14") (pintype "unspecified"))
      (node (ref "U4") (pin "6") (pinfunction "CS#_6") (pintype "unspecified"))
    )
    (net (code "30") (name "/INA+") (class "Default")
      (node (ref "R11") (pin "2") (pinfunction "2_2") (pintype "input"))
      (node (ref "U8") (pin "8") (pinfunction "VIN+_8") (pintype "unspecified"))
      (node (ref "U9") (pin "1") (pinfunction "1_1") (pintype "input"))
    )
    (net (code "31") (name "/INA-") (class "Default")
      (node (ref "R11") (pin "1") (pinfunction "1_1") (pintype "input"))
      (node (ref "U8") (pin "7") (pinfunction "VIN-_7") (pintype "unspecified"))
      (node (ref "U9") (pin "2") (pinfunction "2_2") (pintype "input"))
    )
    (net (code "32") (name "/IP+") (class "Default")
      (node (ref "U18") (pin "1") (pinfunction "IP+_1") (pintype "input"))
      (node (ref "U18") (pin "2") (pinfunction "IP+_2") (pintype "input"))
      (node (ref "U20") (pin "2") (pinfunction "2_2") (pintype "input"))
    )
    (net (code "33") (name "/IP-") (class "Default")
      (node (ref "U18") (pin "3") (pinfunction "IP-_3") (pintype "input"))
      (node (ref "U18") (pin "4") (pinfunction "IP-_4") (pintype "input"))
      (node (ref "U20") (pin "1") (pinfunction "1_1") (pintype "input"))
    )
    (net (code "34") (name "/MISO") (class "Default")
      (node (ref "U1") (pin "16") (pinfunction "(PCINT4/MISO)PB4_16") (pintype "unspecified"))
      (node (ref "U3") (pin "7") (pinfunction "SO_7") (pintype "unspecified"))
      (node (ref "U4") (pin "7") (pinfunction "SO_7") (pintype "unspecified"))
    )
    (net (code "35") (name "/MOSI") (class "Default")
      (node (ref "U1") (pin "15") (pinfunction "(PCINT3/OC2A/MOSI)PB3_15") (pintype "unspecified"))
      (node (ref "U27") (pin "4") (pinfunction "4_4") (pintype "unspecified"))
    )
    (net (code "36") (name "/NO1") (class "Default")
      (node (ref "RLY1") (pin "2") (pinfunction "2_2") (pintype "input"))
      (node (ref "U10") (pin "3") (pinfunction "3_3") (pintype "input"))
    )
    (net (code "37") (name "/NO2") (class "Default")
      (node (ref "RLY2") (pin "2") (pinfunction "2_2") (pintype "input"))
      (node (ref "U10") (pin "1") (pinfunction "1_1") (pintype "input"))
    )
    (net (code "38") (name "/NO3") (class "Default")
      (node (ref "RLY3") (pin "2") (pinfunction "2_2") (pintype "input"))
      (node (ref "U13") (pin "3") (pinfunction "3_3") (pintype "input"))
    )
    (net (code "39") (name "/NO4") (class "Default")
      (node (ref "RLY4") (pin "2") (pinfunction "2_2") (pintype "input"))
      (node (ref "U13") (pin "1") (pinfunction "1_1") (pintype "input"))
    )
    (net (code "40") (name "/NO5") (class "Default")
      (node (ref "RLY5") (pin "2") (pinfunction "2_2") (pintype "input"))
      (node (ref "U14") (pin "3") (pinfunction "3_3") (pintype "input"))
    )
    (net (code "41") (name "/NO6") (class "Default")
      (node (ref "RLY6") (pin "2") (pinfunction "2_2") (pintype "input"))
      (node (ref "U14") (pin "1") (pinfunction "1_1") (pintype "input"))
    )
    (net (code "42") (name "/RESET") (class "Default")
      (node (ref "C13") (pin "1") (pinfunction "1_1") (pintype "input"))
      (node (ref "R7") (pin "1") (pinfunction "1_1") (pintype "input"))
      (node (ref "SW2") (pin "2") (pinfunction "2_2") (pintype "input"))
      (node (ref "U1") (pin "29") (pinfunction "PC6(RESET#/PCINT14)_29") (pintype "unspecified"))
    )
    (net (code "43") (name "/RX") (class "Default")
      (node (ref "H1") (pin "1") (pinfunction "1_1") (pintype "input"))
      (node (ref "R1") (pin "1") (pinfunction "1_1") (pintype "input"))
      (node (ref "U11") (pin "1") (pinfunction "TXD_1") (pintype "unspecified"))
    )
    (net (code "44") (name "/SCK") (class "Default")
      (node (ref "R5") (pin "2") (pinfunction "2_2") (pintype "input"))
      (node (ref "U1") (pin "17") (pinfunction "PB5(SCK/PCINT5)_17") (pintype "unspecified"))
      (node (ref "U3") (pin "5") (pinfunction "SCK_5") (pintype "unspecified"))
      (node (ref "U4") (pin "5") (pinfunction "SCK_5") (pintype "unspecified"))
    )
    (net (code "45") (name "/SCL") (class "Default")
      (node (ref "R8") (pin "2") (pinfunction "2_2") (pintype "input"))
      (node (ref "U1") (pin "28") (pinfunction "PC5(ADC5/SCL/PCINT13)_28") (pintype "unspecified"))
      (node (ref "U23") (pin "4") (pinfunction "4_4") (pintype "unspecified"))
      (node (ref "U24") (pin "4") (pinfunction "4_4") (pintype "unspecified"))
      (node (ref "U8") (pin "4") (pinfunction "SCL_4") (pintype "unspecified"))
    )
    (net (code "46") (name "/SDA") (class "Default")
      (node (ref "R9") (pin "1") (pinfunction "1_1") (pintype "input"))
      (node (ref "U1") (pin "27") (pinfunction "PC4(ADC4/SDA/PCINT12)_27") (pintype "unspecified"))
      (node (ref "U23") (pin "3") (pinfunction "3_3") (pintype "unspecified"))
      (node (ref "U24") (pin "3") (pinfunction "3_3") (pintype "unspecified"))
      (node (ref "U8") (pin "3") (pinfunction "SDA_3") (pintype "unspecified"))
    )
    (net (code "47") (name "/SUPPLY") (class "Default")
      (node (ref "C3") (pin "1") (pinfunction "1_1") (pintype "input"))
      (node (ref "C4") (pin "2") (pinfunction "2_2") (pintype "unspecified"))
      (node (ref "SW1") (pin "2") (pinfunction "2_2") (pintype "input"))
      (node (ref "U6") (pin "1") (pinfunction "VIN_1") (pintype "unspecified"))
    )
    (net (code "48") (name "/T1+") (class "Default")
      (node (ref "U2") (pin "2") (pinfunction "2_2") (pintype "input"))
      (node (ref "U3") (pin "3") (pinfunction "T+_3") (pintype "unspecified"))
    )
    (net (code "49") (name "/T2+") (class "Default")
      (node (ref "U4") (pin "3") (pinfunction "T+_3") (pintype "unspecified"))
      (node (ref "U5") (pin "2") (pinfunction "2_2") (pintype "input"))
    )
    (net (code "50") (name "/TX") (class "Default")
      (node (ref "H2") (pin "1") (pinfunction "1_1") (pintype "input"))
      (node (ref "R2") (pin "1") (pinfunction "1_1") (pintype "input"))
      (node (ref "U11") (pin "5") (pinfunction "RXD_5") (pintype "unspecified"))
    )
    (net (code "51") (name "/VOLTIN") (class "Default")
      (node (ref "F3") (pin "2") (pinfunction "2_2") (pintype "unspecified"))
      (node (ref "R21") (pin "2") (pinfunction "2_2") (pintype "input"))
    )
    (net (code "52") (name "GND") (class "Default")
      (node (ref "C1") (pin "1") (pinfunction "1_1") (pintype "unspecified"))
      (node (ref "C10") (pin "1") (pinfunction "1_1") (pintype "input"))
      (node (ref "C11") (pin "1") (pinfunction "1_1") (pintype "input"))
      (node (ref "C12") (pin "1") (pinfunction "1_1") (pintype "input"))
      (node (ref "C14") (pin "1") (pinfunction "1_1") (pintype "input"))
      (node (ref "C15") (pin "1") (pinfunction "1_1") (pintype "input"))
      (node (ref "C16") (pin "1") (pinfunction "1_1") (pintype "input"))
      (node (ref "C17") (pin "1") (pinfunction "1_1") (pintype "unspecified"))
      (node (ref "C18") (pin "1") (pinfunction "1_1") (pintype "unspecified"))
      (node (ref "C19") (pin "1") (pinfunction "1_1") (pintype "unspecified"))
      (node (ref "C2") (pin "1") (pinfunction "1_1") (pintype "unspecified"))
      (node (ref "C20") (pin "1") (pinfunction "1_1") (pintype "unspecified"))
      (node (ref "C21") (pin "1") (pinfunction "1_1") (pintype "input"))
      (node (ref "C22") (pin "1") (pinfunction "1_1") (pintype "input"))
      (node (ref "C3") (pin "2") (pinfunction "2_2") (pintype "input"))
      (node (ref "C4") (pin "1") (pinfunction "1_1") (pintype "unspecified"))
      (node (ref "C5") (pin "1") (pinfunction "1_1") (pintype "unspecified"))
      (node (ref "C6") (pin "2") (pinfunction "2_2") (pintype "unspecified"))
      (node (ref "C7") (pin "1") (pinfunction "1_1") (pintype "input"))
      (node (ref "C8") (pin "1") (pinfunction "1_1") (pintype "input"))
      (node (ref "C9") (pin "1") (pinfunction "1_1") (pintype "input"))
      (node (ref "D1") (pin "2") (pinfunction "A_2") (pintype "unspecified"))
      (node (ref "LED1") (pin "2") (pinfunction "K_2") (pintype "unspecified"))
      (node (ref "LED10") (pin "2") (pinfunction "K_2") (pintype "unspecified"))
      (node (ref "LED11") (pin "2") (pinfunction "K_2") (pintype "unspecified"))
      (node (ref "LED2") (pin "2") (pinfunction "K_2") (pintype "unspecified"))
      (node (ref "LED7") (pin "2") (pinfunction "K_2") (pintype "unspecified"))
      (node (ref "Q1") (pin "2") (pinfunction "S_2") (pintype "unspecified"))
      (node (ref "Q2") (pin "2") (pinfunction "S_2") (pintype "unspecified"))
      (node (ref "Q3") (pin "2") (pinfunction "S_2") (pintype "unspecified"))
      (node (ref "Q4") (pin "2") (pinfunction "S_2") (pintype "unspecified"))
      (node (ref "Q5") (pin "2") (pinfunction "S_2") (pintype "unspecified"))
      (node (ref "Q6") (pin "2") (pinfunction "S_2") (pintype "unspecified"))
      (node (ref "R10") (pin "2") (pinfunction "2_2") (pintype "input"))
      (node (ref "R12") (pin "2") (pinfunction "2_2") (pintype "input"))
      (node (ref "R19") (pin "2") (pinfunction "2_2") (pintype "input"))
      (node (ref "R20") (pin "2") (pinfunction "2_2") (pintype "input"))
      (node (ref "R22") (pin "1") (pinfunction "1_1") (pintype "input"))
      (node (ref "R27") (pin "2") (pinfunction "2_2") (pintype "input"))
      (node (ref "R28") (pin "2") (pinfunction "2_2") (pintype "input"))
      (node (ref "R38") (pin "1") (pinfunction "1_1") (pintype "input"))
      (node (ref "R4") (pin "1") (pinfunction "1_1") (pintype "input"))
      (node (ref "R42") (pin "2") (pinfunction "2_2") (pintype "input"))
      (node (ref "R43") (pin "2") (pinfunction "2_2") (pintype "input"))
      (node (ref "R45") (pin "2") (pinfunction "2_2") (pintype "input"))
      (node (ref "R6") (pin "1") (pinfunction "1_1") (pintype "input"))
      (node (ref "R6") (pin "2") (pinfunction "2_2") (pintype "input"))
      (node (ref "SW2") (pin "1") (pinfunction "1_1") (pintype "input"))
      (node (ref "TGND1") (pin "1") (pinfunction "1_1") (pintype "unspecified"))
      (node (ref "U1") (pin "21") (pinfunction "GND_21") (pintype "unspecified"))
      (node (ref "U1") (pin "3") (pinfunction "GND_3") (pintype "unspecified"))
      (node (ref "U1") (pin "5") (pinfunction "GND_5") (pintype "unspecified"))
      (node (ref "U11") (pin "18") (pinfunction "GND_18") (pintype "unspecified"))
      (node (ref "U11") (pin "21") (pinfunction "GND_21") (pintype "unspecified"))
      (node (ref "U11") (pin "25") (pinfunction "AGND_25") (pintype "unspecified"))
      (node (ref "U11") (pin "26") (pinfunction "TEST_26") (pintype "unspecified"))
      (node (ref "U11") (pin "7") (pinfunction "GND_7") (pintype "unspecified"))
      (node (ref "U12") (pin "1") (pinfunction "1_1") (pintype "input"))
      (node (ref "U15") (pin "1") (pinfunction "GND_1") (pintype "input"))
      (node (ref "U16") (pin "5") (pinfunction "GND_5") (pintype "unspecified"))
      (node (ref "U18") (pin "5") (pinfunction "GND_5") (pintype "input"))
      (node (ref "U2") (pin "1") (pinfunction "1_1") (pintype "input"))
      (node (ref "U23") (pin "1") (pinfunction "1_1") (pintype "unspecified"))
      (node (ref "U24") (pin "1") (pinfunction "1_1") (pintype "unspecified"))
      (node (ref "U25") (pin "1") (pinfunction "1_1") (pintype "unspecified"))
      (node (ref "U27") (pin "1") (pinfunction "1_1") (pintype "unspecified"))
      (node (ref "U3") (pin "1") (pinfunction "GND_1") (pintype "unspecified"))
      (node (ref "U3") (pin "2") (pinfunction "T-_2") (pintype "unspecified"))
      (node (ref "U4") (pin "1") (pinfunction "GND_1") (pintype "unspecified"))
      (node (ref "U4") (pin "2") (pinfunction "T-_2") (pintype "unspecified"))
      (node (ref "U5") (pin "1") (pinfunction "1_1") (pintype "input"))
      (node (ref "U6") (pin "3") (pinfunction "GND_3") (pintype "unspecified"))
      (node (ref "U6") (pin "5") (pinfunction "ON_OFF_5") (pintype "unspecified"))
      (node (ref "U6") (pin "6") (pinfunction "GND_6") (pintype "unspecified"))
      (node (ref "U7") (pin "1") (pinfunction "1_1") (pintype "input"))
      (node (ref "U8") (pin "6") (pinfunction "GND_6") (pintype "unspecified"))
      (node (ref "USB1") (pin "5") (pinfunction "GND_5") (pintype "unspecified"))
      (node (ref "USB1") (pin "6") (pinfunction "GND_6") (pintype "unspecified"))
      (node (ref "USB1") (pin "7") (pinfunction "GND_7") (pintype "unspecified"))
      (node (ref "USB1") (pin "8") (pinfunction "GND_8") (pintype "unspecified"))
      (node (ref "USB1") (pin "9") (pinfunction "GND_9") (pintype "unspecified"))
      (node (ref "Y1") (pin "2") (pinfunction "VSS_2") (pintype "unspecified"))
    )
    (net (code "53") (name "Net-(D1-K)") (class "Default")
      (node (ref "D1") (pin "1") (pinfunction "K_1") (pintype "unspecified"))
      (node (ref "L1") (pin "1") (pinfunction "1_1") (pintype "unspecified"))
      (node (ref "U6") (pin "2") (pinfunction "OUTPUT_2") (pintype "unspecified"))
    )
    (net (code "54") (name "Net-(D3-A)") (class "Default")
      (node (ref "D3") (pin "2") (pinfunction "A_2") (pintype "unspecified"))
      (node (ref "LED3") (pin "2") (pinfunction "K_2") (pintype "unspecified"))
      (node (ref "Q1") (pin "3") (pinfunction "D_3") (pintype "unspecified"))
      (node (ref "RLY1") (pin "4") (pinfunction "4_4") (pintype "input"))
    )
    (net (code "55") (name "Net-(D4-A)") (class "Default")
      (node (ref "D4") (pin "2") (pinfunction "A_2") (pintype "unspecified"))
      (node (ref "LED4") (pin "2") (pinfunction "K_2") (pintype "unspecified"))
      (node (ref "Q2") (pin "3") (pinfunction "D_3") (pintype "unspecified"))
      (node (ref "RLY2") (pin "4") (pinfunction "4_4") (pintype "input"))
    )
    (net (code "56") (name "Net-(D5-A)") (class "Default")
      (node (ref "D5") (pin "2") (pinfunction "A_2") (pintype "unspecified"))
      (node (ref "LED5") (pin "2") (pinfunction "K_2") (pintype "unspecified"))
      (node (ref "Q3") (pin "3") (pinfunction "D_3") (pintype "unspecified"))
      (node (ref "RLY3") (pin "4") (pinfunction "4_4") (pintype "input"))
    )
    (net (code "57") (name "Net-(D6-A)") (class "Default")
      (node (ref "D6") (pin "2") (pinfunction "A_2") (pintype "unspecified"))
      (node (ref "LED6") (pin "2") (pinfunction "K_2") (pintype "unspecified"))
      (node (ref "Q4") (pin "3") (pinfunction "D_3") (pintype "unspecified"))
      (node (ref "RLY4") (pin "4") (pinfunction "4_4") (pintype "input"))
    )
    (net (code "58") (name "Net-(D7-A)") (class "Default")
      (node (ref "D7") (pin "2") (pinfunction "A_2") (pintype "unspecified"))
      (node (ref "LED8") (pin "2") (pinfunction "K_2") (pintype "unspecified"))
      (node (ref "Q5") (pin "3") (pinfunction "D_3") (pintype "unspecified"))
      (node (ref "RLY5") (pin "4") (pinfunction "4_4") (pintype "input"))
    )
    (net (code "59") (name "Net-(D8-A)") (class "Default")
      (node (ref "D8") (pin "2") (pinfunction "A_2") (pintype "unspecified"))
      (node (ref "LED9") (pin "2") (pinfunction "K_2") (pintype "unspecified"))
      (node (ref "Q6") (pin "3") (pinfunction "D_3") (pintype "unspecified"))
      (node (ref "RLY6") (pin "4") (pinfunction "4_4") (pintype "input"))
    )
    (net (code "60") (name "Net-(F1-Pad1)") (class "Default")
      (node (ref "F1") (pin "1") (pinfunction "1_1") (pintype "unspecified"))
      (node (ref "U7") (pin "2") (pinfunction "2_2") (pintype "input"))
    )
    (net (code "61") (name "Net-(F1-Pad2)") (class "Default")
      (node (ref "F1") (pin "2") (pinfunction "2_2") (pintype "unspecified"))
      (node (ref "SW1") (pin "1") (pinfunction "1_1") (pintype "input"))
    )
    (net (code "62") (name "Net-(F3-Pad1)") (class "Default")
      (node (ref "F3") (pin "1") (pinfunction "1_1") (pintype "unspecified"))
      (node (ref "U12") (pin "2") (pinfunction "2_2") (pintype "input"))
    )
    (net (code "63") (name "Net-(F4-Pad2)") (class "Default")
      (node (ref "F4") (pin "2") (pinfunction "2_2") (pintype "unspecified"))
      (node (ref "U17") (pin "1") (pinfunction "1_1") (pintype "input"))
    )
    (net (code "64") (name "Net-(F5-Pad2)") (class "Default")
      (node (ref "F5") (pin "2") (pinfunction "2_2") (pintype "unspecified"))
      (node (ref "U17") (pin "2") (pinfunction "2_2") (pintype "input"))
    )
    (net (code "65") (name "Net-(LED1-A)") (class "Default")
      (node (ref "LED1") (pin "1") (pinfunction "A_1") (pintype "unspecified"))
      (node (ref "R3") (pin "1") (pinfunction "1_1") (pintype "input"))
    )
    (net (code "66") (name "Net-(LED2-A)") (class "Default")
      (node (ref "LED2") (pin "1") (pinfunction "A_1") (pintype "unspecified"))
      (node (ref "R5") (pin "1") (pinfunction "1_1") (pintype "input"))
    )
    (net (code "67") (name "Net-(LED3-A)") (class "Default")
      (node (ref "LED3") (pin "1") (pinfunction "A_1") (pintype "unspecified"))
      (node (ref "R15") (pin "1") (pinfunction "1_1") (pintype "input"))
    )
    (net (code "68") (name "Net-(LED4-A)") (class "Default")
      (node (ref "LED4") (pin "1") (pinfunction "A_1") (pintype "unspecified"))
      (node (ref "R16") (pin "1") (pinfunction "1_1") (pintype "input"))
    )
    (net (code "69") (name "Net-(LED5-A)") (class "Default")
      (node (ref "LED5") (pin "1") (pinfunction "A_1") (pintype "unspecified"))
      (node (ref "R23") (pin "1") (pinfunction "1_1") (pintype "input"))
    )
    (net (code "70") (name "Net-(LED6-A)") (class "Default")
      (node (ref "LED6") (pin "1") (pinfunction "A_1") (pintype "unspecified"))
      (node (ref "R24") (pin "1") (pinfunction "1_1") (pintype "input"))
    )
    (net (code "71") (name "Net-(LED7-A)") (class "Default")
      (node (ref "LED7") (pin "1") (pinfunction "A_1") (pintype "unspecified"))
      (node (ref "R34") (pin "1") (pinfunction "1_1") (pintype "input"))
    )
    (net (code "72") (name "Net-(LED8-A)") (class "Default")
      (node (ref "LED8") (pin "1") (pinfunction "A_1") (pintype "unspecified"))
      (node (ref "R35") (pin "1") (pinfunction "1_1") (pintype "input"))
    )
    (net (code "73") (name "Net-(LED9-A)") (class "Default")
      (node (ref "LED9") (pin "1") (pinfunction "A_1") (pintype "unspecified"))
      (node (ref "R36") (pin "1") (pinfunction "1_1") (pintype "input"))
    )
    (net (code "74") (name "Net-(LED10-A)") (class "Default")
      (node (ref "LED10") (pin "1") (pinfunction "A_1") (pintype "unspecified"))
      (node (ref "R39") (pin "1") (pinfunction "1_1") (pintype "input"))
    )
    (net (code "75") (name "Net-(LED11-A)") (class "Default")
      (node (ref "LED11") (pin "1") (pinfunction "A_1") (pintype "unspecified"))
      (node (ref "R44") (pin "1") (pinfunction "1_1") (pintype "input"))
    )
    (net (code "76") (name "Net-(LEDRX1--)") (class "Default")
      (node (ref "LEDRX1") (pin "2") (pinfunction "-_2") (pintype "unspecified"))
      (node (ref "R13") (pin "2") (pinfunction "2_2") (pintype "input"))
    )
    (net (code "77") (name "Net-(LEDTX1--)") (class "Default")
      (node (ref "LEDTX1") (pin "2") (pinfunction "-_2") (pintype "unspecified"))
      (node (ref "R14") (pin "2") (pinfunction "2_2") (pintype "input"))
    )
    (net (code "78") (name "Net-(Q1-G)") (class "Default")
      (node (ref "Q1") (pin "1") (pinfunction "G_1") (pintype "unspecified"))
      (node (ref "R17") (pin "2") (pinfunction "2_2") (pintype "input"))
      (node (ref "R19") (pin "1") (pinfunction "1_1") (pintype "input"))
    )
    (net (code "79") (name "Net-(Q2-G)") (class "Default")
      (node (ref "Q2") (pin "1") (pinfunction "G_1") (pintype "unspecified"))
      (node (ref "R18") (pin "2") (pinfunction "2_2") (pintype "input"))
      (node (ref "R20") (pin "1") (pinfunction "1_1") (pintype "input"))
    )
    (net (code "80") (name "Net-(Q3-G)") (class "Default")
      (node (ref "Q3") (pin "1") (pinfunction "G_1") (pintype "unspecified"))
      (node (ref "R25") (pin "2") (pinfunction "2_2") (pintype "input"))
      (node (ref "R27") (pin "1") (pinfunction "1_1") (pintype "input"))
    )
    (net (code "81") (name "Net-(Q4-G)") (class "Default")
      (node (ref "Q4") (pin "1") (pinfunction "G_1") (pintype "unspecified"))
      (node (ref "R26") (pin "2") (pinfunction "2_2") (pintype "input"))
      (node (ref "R28") (pin "1") (pinfunction "1_1") (pintype "input"))
    )
    (net (code "82") (name "Net-(Q5-G)") (class "Default")
      (node (ref "Q5") (pin "1") (pinfunction "G_1") (pintype "unspecified"))
      (node (ref "R40") (pin "2") (pinfunction "2_2") (pintype "input"))
      (node (ref "R42") (pin "1") (pinfunction "1_1") (pintype "input"))
    )
    (net (code "83") (name "Net-(Q6-G)") (class "Default")
      (node (ref "Q6") (pin "1") (pinfunction "G_1") (pintype "unspecified"))
      (node (ref "R41") (pin "2") (pinfunction "2_2") (pintype "input"))
      (node (ref "R43") (pin "1") (pinfunction "1_1") (pintype "input"))
    )
    (net (code "84") (name "Net-(U1-(PCINT6{slash}XTAL1{slash}TOSC1)PB6)") (class "Default")
      (node (ref "U1") (pin "7") (pinfunction "(PCINT6/XTAL1/TOSC1)PB6_7") (pintype "unspecified"))
      (node (ref "Y1") (pin "1") (pinfunction "1_1") (pintype "unspecified"))
    )
    (net (code "85") (name "Net-(U1-(PCINT7{slash}XTAL2{slash}TOSC2)PB7)") (class "Default")
      (node (ref "U1") (pin "8") (pinfunction "(PCINT7/XTAL2/TOSC2)PB7_8") (pintype "unspecified"))
      (node (ref "Y1") (pin "3") (pinfunction "3_3") (pintype "unspecified"))
    )
    (net (code "86") (name "Net-(U1-PD0(RXD{slash}PCINT16))") (class "Default")
      (node (ref "R1") (pin "2") (pinfunction "2_2") (pintype "input"))
      (node (ref "U1") (pin "30") (pinfunction "PD0(RXD/PCINT16)_30") (pintype "unspecified"))
    )
    (net (code "87") (name "Net-(U1-PD1(TXD{slash}PCINT17))") (class "Default")
      (node (ref "R2") (pin "2") (pinfunction "2_2") (pintype "input"))
      (node (ref "U1") (pin "31") (pinfunction "PD1(TXD/PCINT17)_31") (pintype "unspecified"))
    )
    (net (code "88") (name "Net-(U6-FB)") (class "Default")
      (node (ref "PR1") (pin "2") (pinfunction "2_2") (pintype "input"))
      (node (ref "PR1") (pin "3") (pinfunction "3_3") (pintype "input"))
      (node (ref "R4") (pin "2") (pinfunction "2_2") (pintype "input"))
      (node (ref "U6") (pin "4") (pinfunction "FB_4") (pintype "unspecified"))
    )
    (net (code "89") (name "Net-(U8-A0)") (class "Default")
      (node (ref "R12") (pin "1") (pinfunction "1_1") (pintype "input"))
      (node (ref "U8") (pin "2") (pinfunction "A0_2") (pintype "unspecified"))
    )
    (net (code "90") (name "Net-(U8-A1)") (class "Default")
      (node (ref "R10") (pin "1") (pinfunction "1_1") (pintype "input"))
      (node (ref "U8") (pin "1") (pinfunction "A1_1") (pintype "unspecified"))
    )
    (net (code "91") (name "Net-(U11-CBUS0)") (class "Default")
      (node (ref "R13") (pin "1") (pinfunction "1_1") (pintype "input"))
      (node (ref "U11") (pin "23") (pinfunction "CBUS0_23") (pintype "unspecified"))
    )
    (net (code "92") (name "Net-(U11-CBUS1)") (class "Default")
      (node (ref "R14") (pin "1") (pinfunction "1_1") (pintype "input"))
      (node (ref "U11") (pin "22") (pinfunction "CBUS1_22") (pintype "unspecified"))
    )
    (net (code "93") (name "Net-(U11-DTR#)") (class "Default")
      (node (ref "C13") (pin "2") (pinfunction "2_2") (pintype "input"))
      (node (ref "U11") (pin "2") (pinfunction "DTR#_2") (pintype "unspecified"))
    )
    (net (code "94") (name "Net-(U16-DI)") (class "Default")
      (node (ref "H2") (pin "2") (pinfunction "2_2") (pintype "input"))
      (node (ref "R29") (pin "1") (pinfunction "1_1") (pintype "input"))
      (node (ref "U16") (pin "4") (pinfunction "DI_4") (pintype "unspecified"))
    )
    (net (code "95") (name "Net-(U16-RO)") (class "Default")
      (node (ref "H1") (pin "2") (pinfunction "2_2") (pintype "input"))
      (node (ref "R32") (pin "1") (pinfunction "1_1") (pintype "input"))
      (node (ref "U16") (pin "1") (pinfunction "RO_1") (pintype "unspecified"))
    )
    (net (code "96") (name "Net-(U18-FILTER)") (class "Default")
      (node (ref "C21") (pin "2") (pinfunction "2_2") (pintype "input"))
      (node (ref "U18") (pin "6") (pinfunction "FILTER_6") (pintype "input"))
    )
    (net (code "97") (name "Net-(USB1-VBUS)") (class "Default")
      (node (ref "F2") (pin "2") (pinfunction "2_2") (pintype "unspecified"))
      (node (ref "USB1") (pin "1") (pinfunction "VBUS_1") (pintype "unspecified"))
    )
    (net (code "98") (name "VUSB") (class "Default")
      (node (ref "C14") (pin "2") (pinfunction "2_2") (pintype "input"))
      (node (ref "C15") (pin "2") (pinfunction "2_2") (pintype "input"))
      (node (ref "D9") (pin "2") (pinfunction "A_2") (pintype "unspecified"))
      (node (ref "F2") (pin "1") (pinfunction "1_1") (pintype "unspecified"))
    )
    (net (code "99") (name "unconnected-(SCREW1-Pad1)") (class "Default")
      (node (ref "SCREW1") (pin "1") (pinfunction "1_1") (pintype "input+no_connect"))
    )
    (net (code "100") (name "unconnected-(SCREW2-Pad1)") (class "Default")
      (node (ref "SCREW2") (pin "1") (pinfunction "1_1") (pintype "input+no_connect"))
    )
    (net (code "101") (name "unconnected-(SCREW3-Pad1)") (class "Default")
      (node (ref "SCREW3") (pin "1") (pinfunction "1_1") (pintype "input+no_connect"))
    )
    (net (code "102") (name "unconnected-(SCREW4-Pad1)") (class "Default")
      (node (ref "SCREW4") (pin "1") (pinfunction "1_1") (pintype "input+no_connect"))
    )
    (net (code "103") (name "unconnected-(U3-N.C.-Pad8)") (class "Default")
      (node (ref "U3") (pin "8") (pinfunction "N.C._8") (pintype "unspecified+no_connect"))
    )
    (net (code "104") (name "unconnected-(U4-N.C.-Pad8)") (class "Default")
      (node (ref "U4") (pin "8") (pinfunction "N.C._8") (pintype "unspecified+no_connect"))
    )
    (net (code "105") (name "unconnected-(U11-CBUS2-Pad13)") (class "Default")
      (node (ref "U11") (pin "13") (pinfunction "CBUS2_13") (pintype "unspecified+no_connect"))
    )
    (net (code "106") (name "unconnected-(U11-CBUS3-Pad14)") (class "Default")
      (node (ref "U11") (pin "14") (pinfunction "CBUS3_14") (pintype "unspecified+no_connect"))
    )
    (net (code "107") (name "unconnected-(U11-CBUS4-Pad12)") (class "Default")
      (node (ref "U11") (pin "12") (pinfunction "CBUS4_12") (pintype "unspecified+no_connect"))
    )
    (net (code "108") (name "unconnected-(U11-CTS#-Pad11)") (class "Default")
      (node (ref "U11") (pin "11") (pinfunction "CTS#_11") (pintype "unspecified+no_connect"))
    )
    (net (code "109") (name "unconnected-(U11-DCD#-Pad10)") (class "Default")
      (node (ref "U11") (pin "10") (pinfunction "DCD#_10") (pintype "unspecified+no_connect"))
    )
    (net (code "110") (name "unconnected-(U11-DSR#-Pad9)") (class "Default")
      (node (ref "U11") (pin "9") (pinfunction "DSR#_9") (pintype "unspecified+no_connect"))
    )
    (net (code "111") (name "unconnected-(U11-NC-Pad8)") (class "Default")
      (node (ref "U11") (pin "8") (pinfunction "NC_8") (pintype "unspecified+no_connect"))
    )
    (net (code "112") (name "unconnected-(U11-NC-Pad24)") (class "Default")
      (node (ref "U11") (pin "24") (pinfunction "NC_24") (pintype "unspecified+no_connect"))
    )
    (net (code "113") (name "unconnected-(U11-OSCI-Pad27)") (class "Default")
      (node (ref "U11") (pin "27") (pinfunction "OSCI_27") (pintype "unspecified+no_connect"))
    )
    (net (code "114") (name "unconnected-(U11-OSCO-Pad28)") (class "Default")
      (node (ref "U11") (pin "28") (pinfunction "OSCO_28") (pintype "unspecified+no_connect"))
    )
    (net (code "115") (name "unconnected-(U11-RESET#-Pad19)") (class "Default")
      (node (ref "U11") (pin "19") (pinfunction "RESET#_19") (pintype "unspecified+no_connect"))
    )
    (net (code "116") (name "unconnected-(U11-RI#-Pad6)") (class "Default")
      (node (ref "U11") (pin "6") (pinfunction "RI#_6") (pintype "unspecified+no_connect"))
    )
    (net (code "117") (name "unconnected-(U11-RTS#-Pad3)") (class "Default")
      (node (ref "U11") (pin "3") (pinfunction "RTS#_3") (pintype "unspecified+no_connect"))
    )
    (net (code "118") (name "unconnected-(U23-Pad5)") (class "Default")
      (node (ref "U23") (pin "5") (pinfunction "5_5") (pintype "unspecified+no_connect"))
    )
    (net (code "119") (name "unconnected-(U23-Pad6)") (class "Default")
      (node (ref "U23") (pin "6") (pinfunction "6_6") (pintype "unspecified+no_connect"))
    )
    (net (code "120") (name "unconnected-(U24-Pad5)") (class "Default")
      (node (ref "U24") (pin "5") (pinfunction "5_5") (pintype "unspecified+no_connect"))
    )
    (net (code "121") (name "unconnected-(U24-Pad6)") (class "Default")
      (node (ref "U24") (pin "6") (pinfunction "6_6") (pintype "unspecified+no_connect"))
    )
    (net (code "122") (name "unconnected-(U25-Pad4)") (class "Default")
      (node (ref "U25") (pin "4") (pinfunction "4_4") (pintype "unspecified+no_connect"))
    )
    (net (code "123") (name "unconnected-(U25-Pad5)") (class "Default")
      (node (ref "U25") (pin "5") (pinfunction "5_5") (pintype "unspecified+no_connect"))
    )
    (net (code "124") (name "unconnected-(U27-Pad5)") (class "Default")
      (node (ref "U27") (pin "5") (pinfunction "5_5") (pintype "unspecified+no_connect"))
    )
    (net (code "125") (name "unconnected-(U27-Pad6)") (class "Default")
      (node (ref "U27") (pin "6") (pinfunction "6_6") (pintype "unspecified+no_connect"))
    )
    (net (code "126") (name "unconnected-(USB1-ID-Pad4)") (class "Default")
      (node (ref "USB1") (pin "4") (pinfunction "ID_4") (pintype "unspecified+no_connect"))
    )
  )
)
